# Sij2.net
KiCad netlist of a schematic drawn in EAGLE
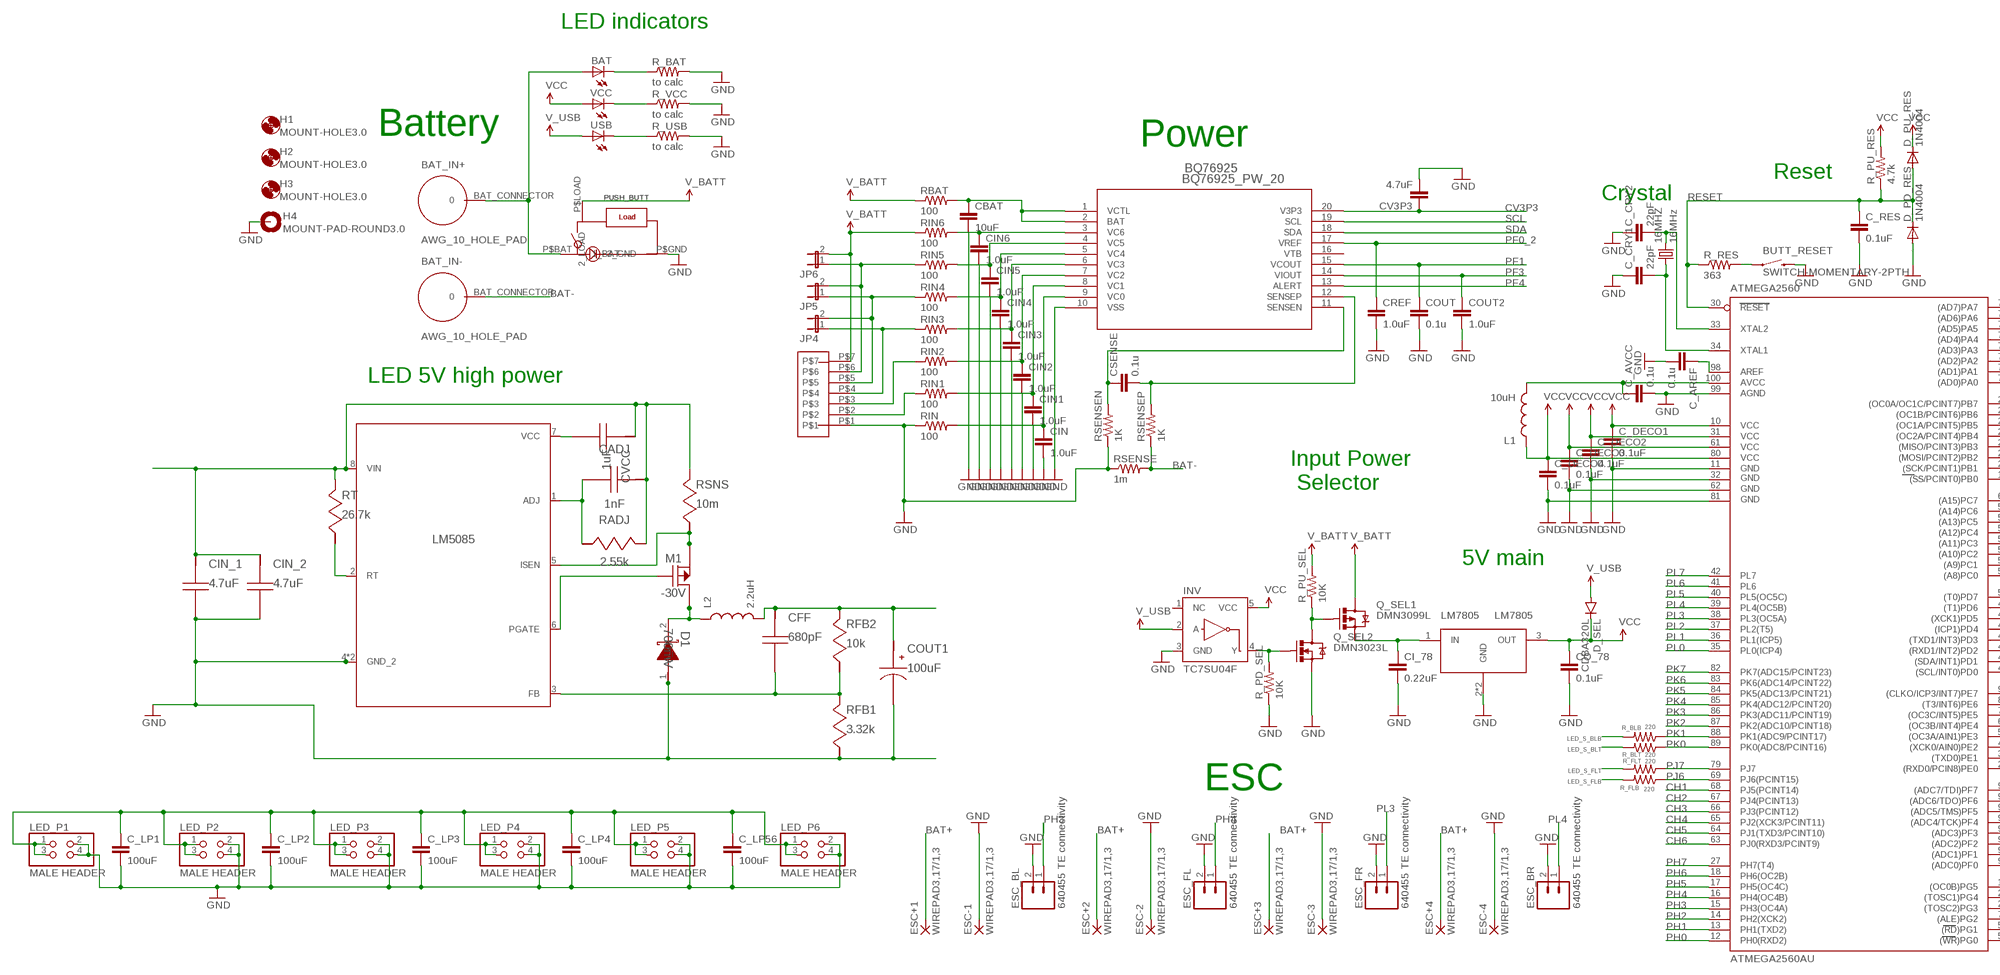
[diagram p0: schematic, sheet 1, part 1 of 2]
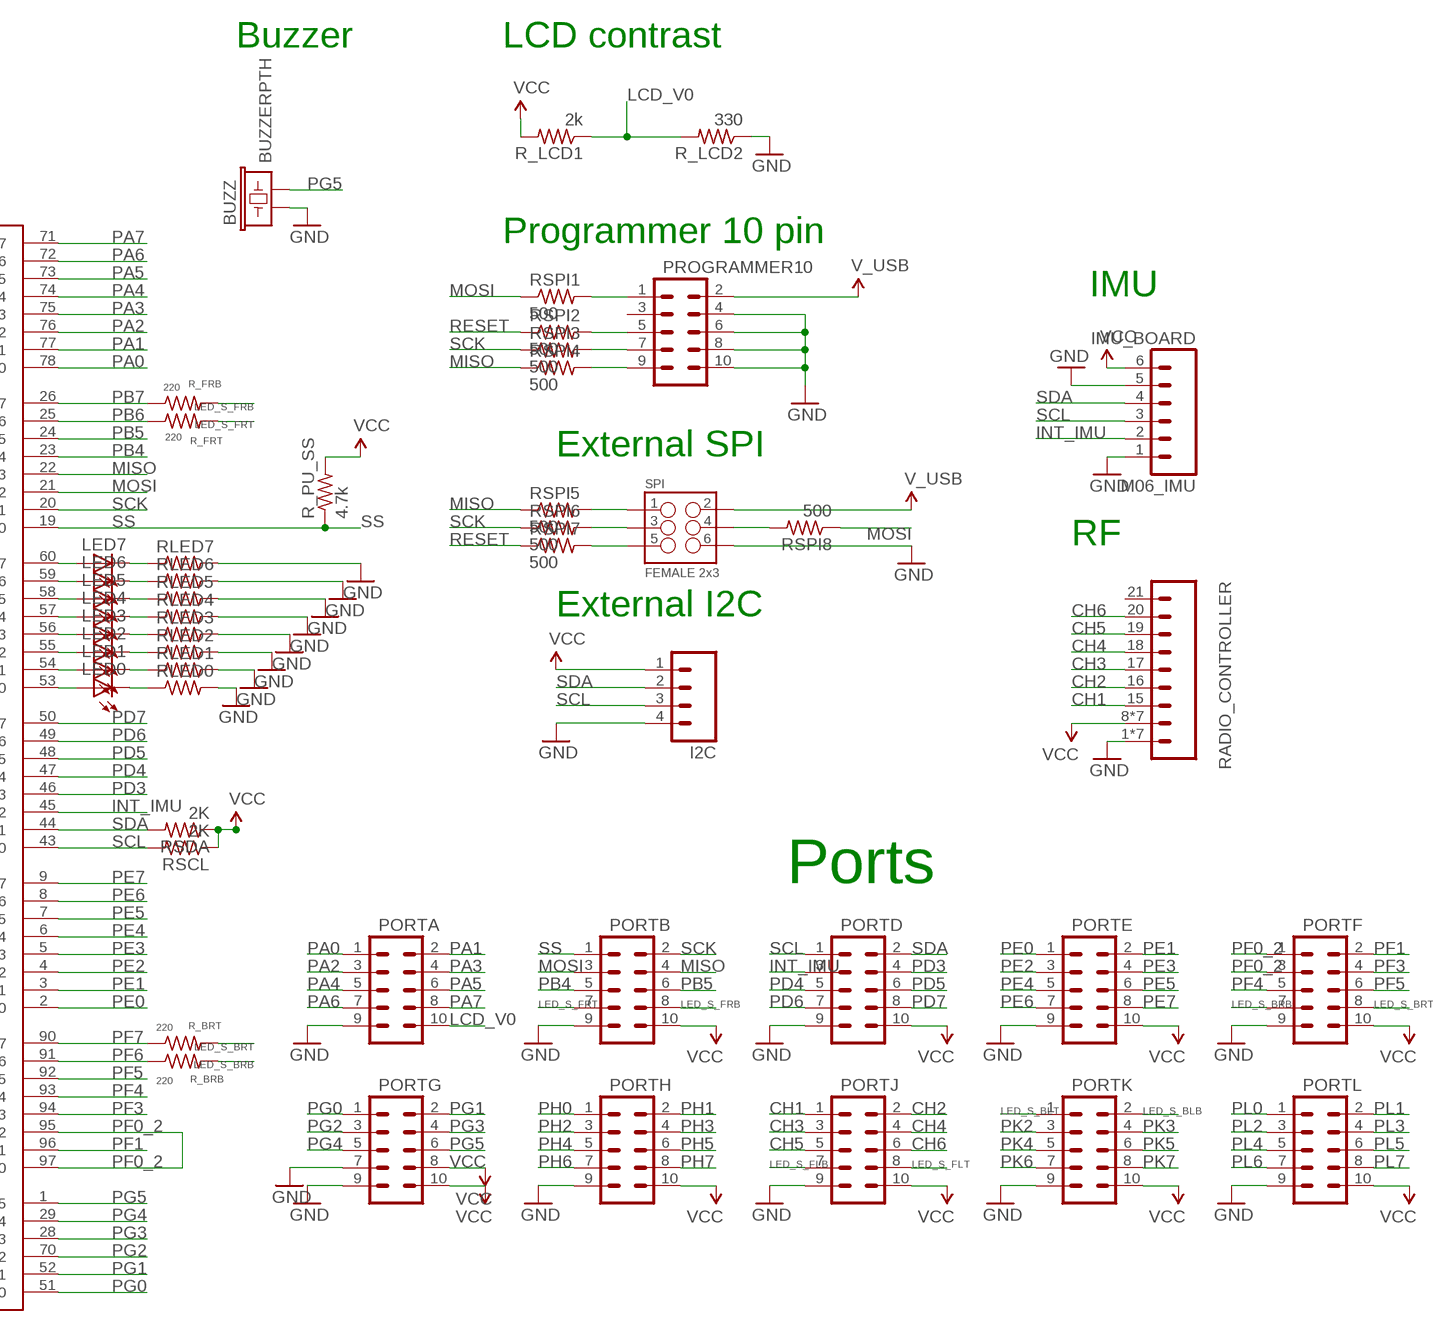
[diagram p1: schematic, sheet 1, part 2 of 2]

(export (version "E")
  (design (tool "Eeschema 10.0.6"))
  (components
    (comp (ref "16MHZ")
      (value "16MHz")
      (footprint "eagle-import:HC49US")
      (libsource (lib "eagle-import") (part "CRYSTALHC49US"))
    )
    (comp (ref "ATMEGA2560")
      (value "ATMEGA2560AU")
      (footprint "eagle-import:TQFP100")
      (libsource (lib "eagle-import") (part "ATMEGA2560AU"))
    )
    (comp (ref "BAT")
      (value "LEDCHIPLED_0805")
      (footprint "eagle-import:CHIPLED_0805")
      (libsource (lib "eagle-import") (part "LEDCHIPLED_0805"))
    )
    (comp (ref "BAT-MONIT")
      (value "7_PIN_JST-XH")
      (footprint "eagle-import:7_PIN_JST-XH")
      (libsource (lib "eagle-import") (part "7_PIN_JST-XH"))
    )
    (comp (ref "BAT_IN+")
      (value "AWG_10_HOLE_PAD")
      (footprint "eagle-import:AWG10_HOLE_PAD")
      (libsource (lib "eagle-import") (part "AWG_10_HOLE_PAD"))
    )
    (comp (ref "BAT_IN-")
      (value "AWG_10_HOLE_PAD")
      (footprint "eagle-import:AWG10_HOLE_PAD")
      (libsource (lib "eagle-import") (part "AWG_10_HOLE_PAD"))
    )
    (comp (ref "BQ76925")
      (value "BQ76925_PW_20")
      (footprint "eagle-import:PW20")
      (fields
        (field (name "GENERIC_PART_NUMBER") "BQ76925")
        (field (name "MANUFACTURER") "Texas Instruments")
        (field (name "MANUFACTURER_PART_NUMBER") "bq76925_pw_20")
      )
      (libsource (lib "eagle-import") (part "BQ76925_PW_20"))
    )
    (comp (ref "BUTT_RESET")
      (value "SWITCH-MOMENTARY-2PTH")
      (footprint "eagle-import:TACTILE-PTH")
      (libsource (lib "eagle-import") (part "SWITCH-MOMENTARY-2PTH"))
    )
    (comp (ref "BUZZ")
      (value "BUZZERPTH")
      (footprint "eagle-import:BUZZER-12MM")
      (libsource (lib "eagle-import") (part "BUZZERPTH"))
    )
    (comp (ref "CADJ")
      (value "1nF")
      (footprint "eagle-import:0201")
      (fields (field (name "MANUFACTURER_PART_NUMBER") "GRM033R71C102KA01D"))
      (libsource (lib "eagle-import") (part "GRM033R71C102KA01D"))
    )
    (comp (ref "CBAT")
      (value "10uF")
      (footprint "eagle-import:0805")
      (libsource (lib "eagle-import") (part "CAP0805"))
    )
    (comp (ref "CFF")
      (value "680pF")
      (footprint "eagle-import:0603")
      (fields (field (name "MANUFACTURER_PART_NUMBER") "GRM188R72E681KW07D"))
      (libsource (lib "eagle-import") (part "GRM188R72E681KW07D"))
    )
    (comp (ref "CIN")
      (value "1.0uF")
      (footprint "eagle-import:0603-CAP")
      (libsource (lib "eagle-import") (part "1.0UF-16V-10%(0603)"))
    )
    (comp (ref "CIN1")
      (value "1.0uF")
      (footprint "eagle-import:0603-CAP")
      (libsource (lib "eagle-import") (part "1.0UF-16V-10%(0603)"))
    )
    (comp (ref "CIN2")
      (value "1.0uF")
      (footprint "eagle-import:0603-CAP")
      (libsource (lib "eagle-import") (part "1.0UF-16V-10%(0603)"))
    )
    (comp (ref "CIN3")
      (value "1.0uF")
      (footprint "eagle-import:0603-CAP")
      (libsource (lib "eagle-import") (part "1.0UF-16V-10%(0603)"))
    )
    (comp (ref "CIN4")
      (value "1.0uF")
      (footprint "eagle-import:0603-CAP")
      (libsource (lib "eagle-import") (part "1.0UF-16V-10%(0603)"))
    )
    (comp (ref "CIN5")
      (value "1.0uF")
      (footprint "eagle-import:0603-CAP")
      (libsource (lib "eagle-import") (part "1.0UF-16V-10%(0603)"))
    )
    (comp (ref "CIN6")
      (value "1.0uF")
      (footprint "eagle-import:0603-CAP")
      (libsource (lib "eagle-import") (part "1.0UF-16V-10%(0603)"))
    )
    (comp (ref "CIN_1")
      (value "4.7uF")
      (footprint "eagle-import:0805")
      (fields (field (name "MANUFACTURER_PART_NUMBER") "GRM21BR61E475MA12L"))
      (libsource (lib "eagle-import") (part "GRM21BR61E475MA12L"))
    )
    (comp (ref "CIN_2")
      (value "4.7uF")
      (footprint "eagle-import:0805")
      (fields (field (name "MANUFACTURER_PART_NUMBER") "GRM21BR61E475MA12L"))
      (libsource (lib "eagle-import") (part "GRM21BR61E475MA12L"))
    )
    (comp (ref "CI_78")
      (value "0.22uF")
      (footprint "eagle-import:0603-CAP")
      (libsource (lib "eagle-import") (part "0.22UF-25V-10%(0603)"))
    )
    (comp (ref "COUT")
      (value "0.1u")
      (footprint "eagle-import:0603-CAP")
      (libsource (lib "eagle-import") (part "CAP0603-CAP"))
    )
    (comp (ref "COUT1")
      (value "100uF")
      (footprint "eagle-import:CAPSMT_6_A09")
      (fields (field (name "MANUFACTURER_PART_NUMBER") "6TPH100MAEA"))
      (libsource (lib "eagle-import") (part "6TPH100MAEA"))
    )
    (comp (ref "COUT2")
      (value "1.0uF")
      (footprint "eagle-import:0603-CAP")
      (libsource (lib "eagle-import") (part "1.0UF-16V-10%(0603)"))
    )
    (comp (ref "CO_78")
      (value "0.1uF")
      (footprint "eagle-import:0603-CAP")
      (libsource (lib "eagle-import") (part "0.1UF-25V-5%(0603)"))
    )
    (comp (ref "CREF")
      (value "1.0uF")
      (footprint "eagle-import:0603-CAP")
      (libsource (lib "eagle-import") (part "1.0UF-16V-10%(0603)"))
    )
    (comp (ref "CSENSE")
      (value "0.1u")
      (footprint "eagle-import:0603-CAP")
      (libsource (lib "eagle-import") (part "SparkFun-Passives_CAP0603-CAP"))
    )
    (comp (ref "CV3P3")
      (value "4.7uF")
      (footprint "eagle-import:0603-CAP")
      (libsource (lib "eagle-import") (part "4.7UF-6.3V-10%(0603)0603"))
    )
    (comp (ref "CVCC")
      (value "1uF")
      (footprint "eagle-import:0603")
      (fields (field (name "MANUFACTURER_PART_NUMBER") "GRM188R61C105KA93D"))
      (libsource (lib "eagle-import") (part "GRM188R61C105KA93D"))
    )
    (comp (ref "C_AREF")
      (value "0.1u")
      (footprint "eagle-import:0603-CAP")
      (libsource (lib "eagle-import") (part "CAP0603-CAP"))
    )
    (comp (ref "C_AVCC")
      (value "0.1u")
      (footprint "eagle-import:0603-CAP")
      (libsource (lib "eagle-import") (part "CAP0603-CAP"))
    )
    (comp (ref "C_CRY1")
      (value "22pF")
      (footprint "eagle-import:0603-CAP")
      (libsource (lib "eagle-import") (part "22PF-50V-5%(0603)"))
    )
    (comp (ref "C_CRY2")
      (value "22pF")
      (footprint "eagle-import:0603-CAP")
      (libsource (lib "eagle-import") (part "22PF-50V-5%(0603)"))
    )
    (comp (ref "C_DECO1")
      (value "0.1uF")
      (footprint "eagle-import:0603-CAP")
      (libsource (lib "eagle-import") (part "0.1UF-25V-5%(0603)"))
    )
    (comp (ref "C_DECO2")
      (value "0.1uF")
      (footprint "eagle-import:0603-CAP")
      (libsource (lib "eagle-import") (part "0.1UF-25V-5%(0603)"))
    )
    (comp (ref "C_DECO3")
      (value "0.1uF")
      (footprint "eagle-import:0603-CAP")
      (libsource (lib "eagle-import") (part "0.1UF-25V-5%(0603)"))
    )
    (comp (ref "C_DECO4")
      (value "0.1uF")
      (footprint "eagle-import:0603-CAP")
      (libsource (lib "eagle-import") (part "0.1UF-25V-5%(0603)"))
    )
    (comp (ref "C_LP1")
      (value "100uF")
      (footprint "eagle-import:1206")
      (libsource (lib "eagle-import") (part "CAP1206"))
    )
    (comp (ref "C_LP2")
      (value "100uF")
      (footprint "eagle-import:1206")
      (libsource (lib "eagle-import") (part "CAP1206"))
    )
    (comp (ref "C_LP3")
      (value "100uF")
      (footprint "eagle-import:1206")
      (libsource (lib "eagle-import") (part "CAP1206"))
    )
    (comp (ref "C_LP4")
      (value "100uF")
      (footprint "eagle-import:1206")
      (libsource (lib "eagle-import") (part "CAP1206"))
    )
    (comp (ref "C_LP56")
      (value "100uF")
      (footprint "eagle-import:1206")
      (libsource (lib "eagle-import") (part "CAP1206"))
    )
    (comp (ref "C_RES")
      (value "0.1uF")
      (footprint "eagle-import:0603-CAP")
      (libsource (lib "eagle-import") (part "0.1UF-25V-5%(0603)"))
    )
    (comp (ref "D1")
      (value "700mV")
      (footprint "eagle-import:DDPAK")
      (fields (field (name "MANUFACTURER_PART_NUMBER") "MBRB745PBF"))
      (libsource (lib "eagle-import") (part "MBRB745PBF"))
    )
    (comp (ref "D_PD_RES")
      (value "1N4004")
      (footprint "eagle-import:DO41-10")
      (libsource (lib "eagle-import") (part "1N4004"))
    )
    (comp (ref "D_PU_RES")
      (value "1N4004")
      (footprint "eagle-import:DO41-10")
      (libsource (lib "eagle-import") (part "1N4004"))
    )
    (comp (ref "D_SEL")
      (value "CDBA320L")
      (footprint "eagle-import:SMA-DIODE_ALT")
      (libsource (lib "eagle-import") (part "DIODESMA-ALT"))
    )
    (comp (ref "ESC+1")
      (value "WIREPAD3,17/1,3")
      (footprint "eagle-import:3,17_1,3")
      (libsource (lib "eagle-import") (part "WIREPAD3,17/1,3"))
    )
    (comp (ref "ESC+2")
      (value "WIREPAD3,17/1,3")
      (footprint "eagle-import:3,17_1,3")
      (libsource (lib "eagle-import") (part "WIREPAD3,17/1,3"))
    )
    (comp (ref "ESC+3")
      (value "WIREPAD3,17/1,3")
      (footprint "eagle-import:3,17_1,3")
      (libsource (lib "eagle-import") (part "WIREPAD3,17/1,3"))
    )
    (comp (ref "ESC+4")
      (value "WIREPAD3,17/1,3")
      (footprint "eagle-import:3,17_1,3")
      (libsource (lib "eagle-import") (part "WIREPAD3,17/1,3"))
    )
    (comp (ref "ESC-1")
      (value "WIREPAD3,17/1,3")
      (footprint "eagle-import:3,17_1,3")
      (libsource (lib "eagle-import") (part "WIREPAD3,17/1,3"))
    )
    (comp (ref "ESC-2")
      (value "WIREPAD3,17/1,3")
      (footprint "eagle-import:3,17_1,3")
      (libsource (lib "eagle-import") (part "WIREPAD3,17/1,3"))
    )
    (comp (ref "ESC-3")
      (value "WIREPAD3,17/1,3")
      (footprint "eagle-import:3,17_1,3")
      (libsource (lib "eagle-import") (part "WIREPAD3,17/1,3"))
    )
    (comp (ref "ESC-4")
      (value "WIREPAD3,17/1,3")
      (footprint "eagle-import:3,17_1,3")
      (libsource (lib "eagle-import") (part "WIREPAD3,17/1,3"))
    )
    (comp (ref "ESC_BL")
      (value "640455 TE connectivity")
      (footprint "eagle-import:1X02")
      (libsource (lib "eagle-import") (part "M02PTH"))
    )
    (comp (ref "ESC_BR")
      (value "640455 TE connectivity")
      (footprint "eagle-import:1X02")
      (libsource (lib "eagle-import") (part "M02PTH"))
    )
    (comp (ref "ESC_FL")
      (value "640455 TE connectivity")
      (footprint "eagle-import:1X02")
      (libsource (lib "eagle-import") (part "M02PTH"))
    )
    (comp (ref "ESC_FR")
      (value "640455 TE connectivity")
      (footprint "eagle-import:1X02")
      (libsource (lib "eagle-import") (part "M02PTH"))
    )
    (comp (ref "H1")
      (value "MOUNT-HOLE3.0")
      (footprint "eagle-import:3,0")
      (libsource (lib "eagle-import") (part "MOUNT-HOLE3.0"))
    )
    (comp (ref "H2")
      (value "MOUNT-HOLE3.0")
      (footprint "eagle-import:3,0")
      (libsource (lib "eagle-import") (part "MOUNT-HOLE3.0"))
    )
    (comp (ref "H3")
      (value "MOUNT-HOLE3.0")
      (footprint "eagle-import:3,0")
      (libsource (lib "eagle-import") (part "MOUNT-HOLE3.0"))
    )
    (comp (ref "H4")
      (value "MOUNT-PAD-ROUND3.0")
      (footprint "eagle-import:3,0-PAD")
      (libsource (lib "eagle-import") (part "MOUNT-PAD-ROUND3.0"))
    )
    (comp (ref "I2C")
      (value "M041X04_NO_SILK")
      (footprint "eagle-import:1X04_NO_SILK")
      (libsource (lib "eagle-import") (part "M041X04_NO_SILK"))
    )
    (comp (ref "IMU_BOARD")
      (value "M06_IMU")
      (footprint "eagle-import:1X06_LONGPADS")
      (libsource (lib "eagle-import") (part "M06_IMU"))
    )
    (comp (ref "INV")
      (value "TC7SU04F")
      (footprint "eagle-import:SOT23-5")
      (libsource (lib "eagle-import") (part "INVERTER_SOT23-5"))
    )
    (comp (ref "JP4")
      (value "JUMPER-2PTH")
      (footprint "eagle-import:1X02")
      (libsource (lib "eagle-import") (part "JUMPER-2PTH"))
    )
    (comp (ref "JP5")
      (value "JUMPER-2PTH")
      (footprint "eagle-import:1X02")
      (libsource (lib "eagle-import") (part "JUMPER-2PTH"))
    )
    (comp (ref "JP6")
      (value "JUMPER-2PTH")
      (footprint "eagle-import:1X02")
      (libsource (lib "eagle-import") (part "JUMPER-2PTH"))
    )
    (comp (ref "L1")
      (value "10uH")
      (footprint "eagle-import:0805")
      (libsource (lib "eagle-import") (part "INDUCTOR0805"))
    )
    (comp (ref "L2")
      (value "2.2uH")
      (footprint "eagle-import:MGV0605")
      (libsource (lib "eagle-import") (part "IND_MGV0605"))
    )
    (comp (ref "LED0")
      (value "LEDCHIPLED_0805")
      (footprint "eagle-import:CHIPLED_0805")
      (libsource (lib "eagle-import") (part "LEDCHIPLED_0805"))
    )
    (comp (ref "LED1")
      (value "LEDCHIPLED_0805")
      (footprint "eagle-import:CHIPLED_0805")
      (libsource (lib "eagle-import") (part "LEDCHIPLED_0805"))
    )
    (comp (ref "LED2")
      (value "LEDCHIPLED_0805")
      (footprint "eagle-import:CHIPLED_0805")
      (libsource (lib "eagle-import") (part "LEDCHIPLED_0805"))
    )
    (comp (ref "LED3")
      (value "LEDCHIPLED_0805")
      (footprint "eagle-import:CHIPLED_0805")
      (libsource (lib "eagle-import") (part "LEDCHIPLED_0805"))
    )
    (comp (ref "LED4")
      (value "LEDCHIPLED_0805")
      (footprint "eagle-import:CHIPLED_0805")
      (libsource (lib "eagle-import") (part "LEDCHIPLED_0805"))
    )
    (comp (ref "LED5")
      (value "LEDCHIPLED_0805")
      (footprint "eagle-import:CHIPLED_0805")
      (libsource (lib "eagle-import") (part "LEDCHIPLED_0805"))
    )
    (comp (ref "LED6")
      (value "LEDCHIPLED_0805")
      (footprint "eagle-import:CHIPLED_0805")
      (libsource (lib "eagle-import") (part "LEDCHIPLED_0805"))
    )
    (comp (ref "LED7")
      (value "LEDCHIPLED_0805")
      (footprint "eagle-import:CHIPLED_0805")
      (libsource (lib "eagle-import") (part "LEDCHIPLED_0805"))
    )
    (comp (ref "LED_P1")
      (value "MALE HEADER")
      (footprint "eagle-import:2X02")
      (libsource (lib "eagle-import") (part "PINHD-2X2"))
    )
    (comp (ref "LED_P2")
      (value "MALE HEADER")
      (footprint "eagle-import:2X02")
      (libsource (lib "eagle-import") (part "PINHD-2X2"))
    )
    (comp (ref "LED_P3")
      (value "MALE HEADER")
      (footprint "eagle-import:2X02")
      (libsource (lib "eagle-import") (part "PINHD-2X2"))
    )
    (comp (ref "LED_P4")
      (value "MALE HEADER")
      (footprint "eagle-import:2X02")
      (libsource (lib "eagle-import") (part "PINHD-2X2"))
    )
    (comp (ref "LED_P5")
      (value "MALE HEADER")
      (footprint "eagle-import:2X02")
      (libsource (lib "eagle-import") (part "PINHD-2X2"))
    )
    (comp (ref "LED_P6")
      (value "MALE HEADER")
      (footprint "eagle-import:2X02")
      (libsource (lib "eagle-import") (part "PINHD-2X2"))
    )
    (comp (ref "LM5085")
      (value "LM5085MY/NOPB")
      (footprint "eagle-import:MUY08A")
      (libsource (lib "eagle-import") (part "LM5085MY/NOPB"))
    )
    (comp (ref "LM7805")
      (value "LM7805")
      (footprint "eagle-import:KTT3")
      (libsource (lib "eagle-import") (part "LM7805"))
    )
    (comp (ref "M1")
      (value "-30V")
      (footprint "eagle-import:POWERPAK_SO-8")
      (fields (field (name "MANUFACTURER_PART_NUMBER") "Si7149DP"))
      (libsource (lib "eagle-import") (part "SI7149DP"))
    )
    (comp (ref "PORTA")
      (value "M05X2PTH")
      (footprint "eagle-import:AVR_ICSP")
      (libsource (lib "eagle-import") (part "M05X2PTH"))
    )
    (comp (ref "PORTB")
      (value "M05X2PTH")
      (footprint "eagle-import:AVR_ICSP")
      (libsource (lib "eagle-import") (part "M05X2PTH"))
    )
    (comp (ref "PORTD")
      (value "M05X2PTH")
      (footprint "eagle-import:AVR_ICSP")
      (libsource (lib "eagle-import") (part "M05X2PTH"))
    )
    (comp (ref "PORTE")
      (value "M05X2PTH")
      (footprint "eagle-import:AVR_ICSP")
      (libsource (lib "eagle-import") (part "M05X2PTH"))
    )
    (comp (ref "PORTF")
      (value "M05X2PTH")
      (footprint "eagle-import:AVR_ICSP")
      (libsource (lib "eagle-import") (part "M05X2PTH"))
    )
    (comp (ref "PORTG")
      (value "M05X2PTH")
      (footprint "eagle-import:AVR_ICSP")
      (libsource (lib "eagle-import") (part "M05X2PTH"))
    )
    (comp (ref "PORTH")
      (value "M05X2PTH")
      (footprint "eagle-import:AVR_ICSP")
      (libsource (lib "eagle-import") (part "M05X2PTH"))
    )
    (comp (ref "PORTJ")
      (value "M05X2PTH")
      (footprint "eagle-import:AVR_ICSP")
      (libsource (lib "eagle-import") (part "M05X2PTH"))
    )
    (comp (ref "PORTK")
      (value "M05X2PTH")
      (footprint "eagle-import:AVR_ICSP")
      (libsource (lib "eagle-import") (part "M05X2PTH"))
    )
    (comp (ref "PORTL")
      (value "M05X2PTH")
      (footprint "eagle-import:AVR_ICSP")
      (libsource (lib "eagle-import") (part "M05X2PTH"))
    )
    (comp (ref "PROGRAMMER10")
      (value "M05X2PTH")
      (footprint "eagle-import:AVR_ICSP")
      (libsource (lib "eagle-import") (part "M05X2PTH"))
    )
    (comp (ref "PUSH_BUTT")
      (value "PUSH_BUTTON")
      (footprint "eagle-import:PUSH_BUTTON")
      (libsource (lib "eagle-import") (part "PUSH_BUTTON"))
    )
    (comp (ref "Q_SEL1")
      (value "DMN3099L")
      (footprint "eagle-import:SOT23-3")
      (libsource (lib "eagle-import") (part "MOSFET-PCHANNEL"))
    )
    (comp (ref "Q_SEL2")
      (value "DMN3023L")
      (footprint "eagle-import:SOT23-3")
      (libsource (lib "eagle-import") (part "MOSFET-NCHANNELAO3404A"))
    )
    (comp (ref "RADIO_CONTROLLER")
      (value "RF_CONTROL_3X7_CON")
      (footprint "eagle-import:3X07")
      (libsource (lib "eagle-import") (part "RF_CONTROL_3X7_CON"))
    )
    (comp (ref "RADJ")
      (value "2.55k")
      (footprint "eagle-import:0603")
      (libsource (lib "eagle-import") (part "CRCW04022K55FKED"))
    )
    (comp (ref "RBAT")
      (value "100")
      (footprint "eagle-import:R0603")
      (libsource (lib "eagle-import") (part "R-US_R0603"))
    )
    (comp (ref "RFB1")
      (value "3.32k")
      (footprint "eagle-import:0603")
      (libsource (lib "eagle-import") (part "CRCW04023K32FKED"))
    )
    (comp (ref "RFB2")
      (value "10k")
      (footprint "eagle-import:0603")
      (libsource (lib "eagle-import") (part "CRCW040210K0FKED"))
    )
    (comp (ref "RIN")
      (value "100")
      (footprint "eagle-import:R0603")
      (libsource (lib "eagle-import") (part "R-US_R0603"))
    )
    (comp (ref "RIN1")
      (value "100")
      (footprint "eagle-import:R0603")
      (libsource (lib "eagle-import") (part "R-US_R0603"))
    )
    (comp (ref "RIN2")
      (value "100")
      (footprint "eagle-import:R0603")
      (libsource (lib "eagle-import") (part "R-US_R0603"))
    )
    (comp (ref "RIN3")
      (value "100")
      (footprint "eagle-import:R0603")
      (libsource (lib "eagle-import") (part "R-US_R0603"))
    )
    (comp (ref "RIN4")
      (value "100")
      (footprint "eagle-import:R0603")
      (libsource (lib "eagle-import") (part "R-US_R0603"))
    )
    (comp (ref "RIN5")
      (value "100")
      (footprint "eagle-import:R0603")
      (libsource (lib "eagle-import") (part "R-US_R0603"))
    )
    (comp (ref "RIN6")
      (value "100")
      (footprint "eagle-import:R0603")
      (libsource (lib "eagle-import") (part "R-US_R0603"))
    )
    (comp (ref "RLED0")
      (value "R-US_R0603")
      (footprint "eagle-import:R0603")
      (libsource (lib "eagle-import") (part "R-US_R0603"))
    )
    (comp (ref "RLED1")
      (value "R-US_R0603")
      (footprint "eagle-import:R0603")
      (libsource (lib "eagle-import") (part "R-US_R0603"))
    )
    (comp (ref "RLED2")
      (value "R-US_R0603")
      (footprint "eagle-import:R0603")
      (libsource (lib "eagle-import") (part "R-US_R0603"))
    )
    (comp (ref "RLED3")
      (value "R-US_R0603")
      (footprint "eagle-import:R0603")
      (libsource (lib "eagle-import") (part "R-US_R0603"))
    )
    (comp (ref "RLED4")
      (value "R-US_R0603")
      (footprint "eagle-import:R0603")
      (libsource (lib "eagle-import") (part "R-US_R0603"))
    )
    (comp (ref "RLED5")
      (value "R-US_R0603")
      (footprint "eagle-import:R0603")
      (libsource (lib "eagle-import") (part "R-US_R0603"))
    )
    (comp (ref "RLED6")
      (value "R-US_R0603")
      (footprint "eagle-import:R0603")
      (libsource (lib "eagle-import") (part "R-US_R0603"))
    )
    (comp (ref "RLED7")
      (value "R-US_R0603")
      (footprint "eagle-import:R0603")
      (libsource (lib "eagle-import") (part "R-US_R0603"))
    )
    (comp (ref "RSCL")
      (value "2K")
      (footprint "eagle-import:R0603")
      (libsource (lib "eagle-import") (part "R-US_R0603"))
    )
    (comp (ref "RSDA")
      (value "2K")
      (footprint "eagle-import:R0603")
      (libsource (lib "eagle-import") (part "R-US_R0603"))
    )
    (comp (ref "RSENSE")
      (value "1m")
      (footprint "eagle-import:R1206")
      (libsource (lib "eagle-import") (part "R-US_R1206"))
    )
    (comp (ref "RSENSEN")
      (value "1K")
      (footprint "eagle-import:R0603")
      (libsource (lib "eagle-import") (part "R-US_R0603"))
    )
    (comp (ref "RSENSEP")
      (value "1K")
      (footprint "eagle-import:R0603")
      (libsource (lib "eagle-import") (part "R-US_R0603"))
    )
    (comp (ref "RSNS")
      (value "10m")
      (footprint "eagle-import:1206")
      (fields
        (field (name "MANUFACTURER_PART_NUMBER") "CSR1206FK10L0")
        (field (name "POWER") "0.5")
        (field (name "TOLERANCE") "1.0")
      )
      (libsource (lib "eagle-import") (part "CSR1206FK10L0"))
    )
    (comp (ref "RSPI1")
      (value "500")
      (footprint "eagle-import:R0603")
      (libsource (lib "eagle-import") (part "R-US_R0603"))
    )
    (comp (ref "RSPI2")
      (value "500")
      (footprint "eagle-import:R0603")
      (libsource (lib "eagle-import") (part "R-US_R0603"))
    )
    (comp (ref "RSPI3")
      (value "500")
      (footprint "eagle-import:R0603")
      (libsource (lib "eagle-import") (part "R-US_R0603"))
    )
    (comp (ref "RSPI4")
      (value "500")
      (footprint "eagle-import:R0603")
      (libsource (lib "eagle-import") (part "R-US_R0603"))
    )
    (comp (ref "RSPI5")
      (value "500")
      (footprint "eagle-import:R0603")
      (libsource (lib "eagle-import") (part "R-US_R0603"))
    )
    (comp (ref "RSPI6")
      (value "500")
      (footprint "eagle-import:R0603")
      (libsource (lib "eagle-import") (part "R-US_R0603"))
    )
    (comp (ref "RSPI7")
      (value "500")
      (footprint "eagle-import:R0603")
      (libsource (lib "eagle-import") (part "R-US_R0603"))
    )
    (comp (ref "RSPI8")
      (value "500")
      (footprint "eagle-import:R0603")
      (libsource (lib "eagle-import") (part "R-US_R0603"))
    )
    (comp (ref "RT")
      (value "26.7k")
      (footprint "eagle-import:0603")
      (libsource (lib "eagle-import") (part "CRCW040226K7FKED"))
    )
    (comp (ref "R_BAT")
      (value "to calc")
      (footprint "eagle-import:R0603")
      (libsource (lib "eagle-import") (part "R-US_R0603"))
    )
    (comp (ref "R_BLB")
      (value "220")
      (footprint "eagle-import:R0603")
      (libsource (lib "eagle-import") (part "R-US_R0603"))
    )
    (comp (ref "R_BLT")
      (value "220")
      (footprint "eagle-import:R0603")
      (libsource (lib "eagle-import") (part "R-US_R0603"))
    )
    (comp (ref "R_BRB")
      (value "220")
      (footprint "eagle-import:R0603")
      (libsource (lib "eagle-import") (part "R-US_R0603"))
    )
    (comp (ref "R_BRT")
      (value "220")
      (footprint "eagle-import:R0603")
      (libsource (lib "eagle-import") (part "R-US_R0603"))
    )
    (comp (ref "R_FLB")
      (value "220")
      (footprint "eagle-import:R0603")
      (libsource (lib "eagle-import") (part "R-US_R0603"))
    )
    (comp (ref "R_FLT")
      (value "220")
      (footprint "eagle-import:R0603")
      (libsource (lib "eagle-import") (part "R-US_R0603"))
    )
    (comp (ref "R_FRB")
      (value "220")
      (footprint "eagle-import:R0603")
      (libsource (lib "eagle-import") (part "R-US_R0603"))
    )
    (comp (ref "R_FRT")
      (value "220")
      (footprint "eagle-import:R0603")
      (libsource (lib "eagle-import") (part "R-US_R0603"))
    )
    (comp (ref "R_LCD1")
      (value "2k")
      (footprint "eagle-import:R0603")
      (libsource (lib "eagle-import") (part "R-US_R0603"))
    )
    (comp (ref "R_LCD2")
      (value "330")
      (footprint "eagle-import:R0603")
      (libsource (lib "eagle-import") (part "R-US_R0603"))
    )
    (comp (ref "R_PD_SEL")
      (value "10K")
      (footprint "eagle-import:R0603")
      (libsource (lib "eagle-import") (part "R-US_R0603"))
    )
    (comp (ref "R_PU_RES")
      (value "4.7k")
      (footprint "eagle-import:R0603")
      (libsource (lib "eagle-import") (part "R-US_R0603"))
    )
    (comp (ref "R_PU_SEL")
      (value "10K")
      (footprint "eagle-import:R0603")
      (libsource (lib "eagle-import") (part "R-US_R0603"))
    )
    (comp (ref "R_PU_SS")
      (value "4.7k")
      (footprint "eagle-import:R0603")
      (libsource (lib "eagle-import") (part "R-US_R0603"))
    )
    (comp (ref "R_RES")
      (value "363")
      (footprint "eagle-import:R0603")
      (libsource (lib "eagle-import") (part "R-US_R0603"))
    )
    (comp (ref "R_USB")
      (value "to calc")
      (footprint "eagle-import:R0603")
      (libsource (lib "eagle-import") (part "R-US_R0603"))
    )
    (comp (ref "R_VCC")
      (value "to calc")
      (footprint "eagle-import:R0603")
      (libsource (lib "eagle-import") (part "R-US_R0603"))
    )
    (comp (ref "SPI")
      (value "FEMALE 2x3")
      (footprint "eagle-import:2X3")
      (libsource (lib "eagle-import") (part "M03X2FEMALE"))
    )
    (comp (ref "USB")
      (value "LEDCHIPLED_0805")
      (footprint "eagle-import:CHIPLED_0805")
      (libsource (lib "eagle-import") (part "LEDCHIPLED_0805"))
    )
    (comp (ref "VCC")
      (value "LEDCHIPLED_0805")
      (footprint "eagle-import:CHIPLED_0805")
      (libsource (lib "eagle-import") (part "LEDCHIPLED_0805"))
    )
  )
  (nets
    (net (code "1") (name "/BAT+") (class "Default")
      (node (ref "BAT") (pin "A") (pinfunction "A_A") (pintype "passive"))
      (node (ref "BAT_IN+") (pin "BAT_CONNECTOR") (pinfunction "0_BAT_CONNECTOR") (pintype "bidirectional"))
      (node (ref "ESC+1") (pin "1") (pinfunction "P_1") (pintype "passive"))
      (node (ref "ESC+2") (pin "1") (pinfunction "P_1") (pintype "passive"))
      (node (ref "ESC+3") (pin "1") (pinfunction "P_1") (pintype "passive"))
      (node (ref "ESC+4") (pin "1") (pinfunction "P_1") (pintype "passive"))
      (node (ref "PUSH_BUTT") (pin "P$BAT") (pinfunction "1_BAT_P$BAT") (pintype "bidirectional"))
    )
    (net (code "2") (name "/BAT-") (class "Default")
      (node (ref "BAT_IN-") (pin "BAT_CONNECTOR") (pinfunction "0_BAT_CONNECTOR") (pintype "bidirectional"))
      (node (ref "RSENSE") (pin "2") (pinfunction "2_2") (pintype "passive"))
      (node (ref "RSENSEP") (pin "1") (pinfunction "1_1") (pintype "passive"))
    )
    (net (code "3") (name "/CH1") (class "Default")
      (node (ref "ATMEGA2560") (pin "68") (pinfunction "PJ5(PCINT14)_68") (pintype "bidirectional"))
      (node (ref "PORTJ") (pin "1") (pinfunction "1_1") (pintype "passive"))
      (node (ref "RADIO_CONTROLLER") (pin "15") (pinfunction "1_15") (pintype "bidirectional"))
    )
    (net (code "4") (name "/CH2") (class "Default")
      (node (ref "ATMEGA2560") (pin "67") (pinfunction "PJ4(PCINT13)_67") (pintype "bidirectional"))
      (node (ref "PORTJ") (pin "2") (pinfunction "2_2") (pintype "passive"))
      (node (ref "RADIO_CONTROLLER") (pin "16") (pinfunction "2_16") (pintype "bidirectional"))
    )
    (net (code "5") (name "/CH3") (class "Default")
      (node (ref "ATMEGA2560") (pin "66") (pinfunction "PJ3(PCINT12)_66") (pintype "bidirectional"))
      (node (ref "PORTJ") (pin "3") (pinfunction "3_3") (pintype "passive"))
      (node (ref "RADIO_CONTROLLER") (pin "17") (pinfunction "3_17") (pintype "bidirectional"))
    )
    (net (code "6") (name "/CH4") (class "Default")
      (node (ref "ATMEGA2560") (pin "65") (pinfunction "PJ2(XCK3/PCINT11)_65") (pintype "bidirectional"))
      (node (ref "PORTJ") (pin "4") (pinfunction "4_4") (pintype "passive"))
      (node (ref "RADIO_CONTROLLER") (pin "18") (pinfunction "4_18") (pintype "bidirectional"))
    )
    (net (code "7") (name "/CH5") (class "Default")
      (node (ref "ATMEGA2560") (pin "64") (pinfunction "PJ1(TXD3/PCINT10)_64") (pintype "bidirectional"))
      (node (ref "PORTJ") (pin "5") (pinfunction "5_5") (pintype "passive"))
      (node (ref "RADIO_CONTROLLER") (pin "19") (pinfunction "5_19") (pintype "bidirectional"))
    )
    (net (code "8") (name "/CH6") (class "Default")
      (node (ref "ATMEGA2560") (pin "63") (pinfunction "PJ0(RXD3/PCINT9)_63") (pintype "bidirectional"))
      (node (ref "PORTJ") (pin "6") (pinfunction "6_6") (pintype "passive"))
      (node (ref "RADIO_CONTROLLER") (pin "20") (pinfunction "6_20") (pintype "bidirectional"))
    )
    (net (code "9") (name "/CV3P3") (class "Default")
      (node (ref "BQ76925") (pin "20") (pinfunction "V3P3_20") (pintype "output"))
      (node (ref "CV3P3") (pin "1") (pinfunction "1_1") (pintype "passive"))
    )
    (net (code "10") (name "/INT_IMU") (class "Default")
      (node (ref "ATMEGA2560") (pin "45") (pinfunction "(RXD1/INT2)PD2_45") (pintype "bidirectional"))
      (node (ref "IMU_BOARD") (pin "2") (pinfunction "2_2") (pintype "passive"))
      (node (ref "PORTD") (pin "3") (pinfunction "3_3") (pintype "passive"))
    )
    (net (code "11") (name "/LCD_V0") (class "Default")
      (node (ref "PORTA") (pin "10") (pinfunction "10_10") (pintype "passive"))
      (node (ref "R_LCD1") (pin "1") (pinfunction "1_1") (pintype "passive"))
      (node (ref "R_LCD2") (pin "2") (pinfunction "2_2") (pintype "passive"))
    )
    (net (code "12") (name "/LED_S_BLB") (class "Default")
      (node (ref "PORTK") (pin "2") (pinfunction "2_2") (pintype "passive"))
      (node (ref "R_BLB") (pin "2") (pinfunction "2_2") (pintype "passive"))
    )
    (net (code "13") (name "/LED_S_BLT") (class "Default")
      (node (ref "PORTK") (pin "1") (pinfunction "1_1") (pintype "passive"))
      (node (ref "R_BLT") (pin "2") (pinfunction "2_2") (pintype "passive"))
    )
    (net (code "14") (name "/LED_S_BRB") (class "Default")
      (node (ref "PORTF") (pin "7") (pinfunction "7_7") (pintype "passive"))
      (node (ref "R_BRB") (pin "2") (pinfunction "2_2") (pintype "passive"))
    )
    (net (code "15") (name "/LED_S_BRT") (class "Default")
      (node (ref "PORTF") (pin "8") (pinfunction "8_8") (pintype "passive"))
      (node (ref "R_BRT") (pin "2") (pinfunction "2_2") (pintype "passive"))
    )
    (net (code "16") (name "/LED_S_FLB") (class "Default")
      (node (ref "PORTJ") (pin "7") (pinfunction "7_7") (pintype "passive"))
      (node (ref "R_FLB") (pin "2") (pinfunction "2_2") (pintype "passive"))
    )
    (net (code "17") (name "/LED_S_FLT") (class "Default")
      (node (ref "PORTJ") (pin "8") (pinfunction "8_8") (pintype "passive"))
      (node (ref "R_FLT") (pin "2") (pinfunction "2_2") (pintype "passive"))
    )
    (net (code "18") (name "/LED_S_FRB") (class "Default")
      (node (ref "PORTB") (pin "8") (pinfunction "8_8") (pintype "passive"))
      (node (ref "R_FRB") (pin "2") (pinfunction "2_2") (pintype "passive"))
    )
    (net (code "19") (name "/LED_S_FRT") (class "Default")
      (node (ref "PORTB") (pin "7") (pinfunction "7_7") (pintype "passive"))
      (node (ref "R_FRT") (pin "2") (pinfunction "2_2") (pintype "passive"))
    )
    (net (code "20") (name "/MISO") (class "Default")
      (node (ref "ATMEGA2560") (pin "22") (pinfunction "(MISO/PCINT3)PB3_22") (pintype "bidirectional"))
      (node (ref "PORTB") (pin "4") (pinfunction "4_4") (pintype "passive"))
      (node (ref "RSPI4") (pin "1") (pinfunction "1_1") (pintype "passive"))
      (node (ref "RSPI5") (pin "1") (pinfunction "1_1") (pintype "passive"))
    )
    (net (code "21") (name "/MOSI") (class "Default")
      (node (ref "ATMEGA2560") (pin "21") (pinfunction "(MOSI/PCINT2)PB2_21") (pintype "bidirectional"))
      (node (ref "PORTB") (pin "3") (pinfunction "3_3") (pintype "passive"))
      (node (ref "RSPI1") (pin "1") (pinfunction "1_1") (pintype "passive"))
      (node (ref "RSPI8") (pin "1") (pinfunction "1_1") (pintype "passive"))
    )
    (net (code "22") (name "/PA0") (class "Default")
      (node (ref "ATMEGA2560") (pin "78") (pinfunction "(AD0)PA0_78") (pintype "bidirectional"))
      (node (ref "PORTA") (pin "1") (pinfunction "1_1") (pintype "passive"))
    )
    (net (code "23") (name "/PA1") (class "Default")
      (node (ref "ATMEGA2560") (pin "77") (pinfunction "(AD1)PA1_77") (pintype "bidirectional"))
      (node (ref "PORTA") (pin "2") (pinfunction "2_2") (pintype "passive"))
    )
    (net (code "24") (name "/PA2") (class "Default")
      (node (ref "ATMEGA2560") (pin "76") (pinfunction "(AD2)PA2_76") (pintype "bidirectional"))
      (node (ref "PORTA") (pin "3") (pinfunction "3_3") (pintype "passive"))
    )
    (net (code "25") (name "/PA3") (class "Default")
      (node (ref "ATMEGA2560") (pin "75") (pinfunction "(AD3)PA3_75") (pintype "bidirectional"))
      (node (ref "PORTA") (pin "4") (pinfunction "4_4") (pintype "passive"))
    )
    (net (code "26") (name "/PA4") (class "Default")
      (node (ref "ATMEGA2560") (pin "74") (pinfunction "(AD4)PA4_74") (pintype "bidirectional"))
      (node (ref "PORTA") (pin "5") (pinfunction "5_5") (pintype "passive"))
    )
    (net (code "27") (name "/PA5") (class "Default")
      (node (ref "ATMEGA2560") (pin "73") (pinfunction "(AD5)PA5_73") (pintype "bidirectional"))
      (node (ref "PORTA") (pin "6") (pinfunction "6_6") (pintype "passive"))
    )
    (net (code "28") (name "/PA6") (class "Default")
      (node (ref "ATMEGA2560") (pin "72") (pinfunction "(AD6)PA6_72") (pintype "bidirectional"))
      (node (ref "PORTA") (pin "7") (pinfunction "7_7") (pintype "passive"))
    )
    (net (code "29") (name "/PA7") (class "Default")
      (node (ref "ATMEGA2560") (pin "71") (pinfunction "(AD7)PA7_71") (pintype "bidirectional"))
      (node (ref "PORTA") (pin "8") (pinfunction "8_8") (pintype "passive"))
    )
    (net (code "30") (name "/PB4") (class "Default")
      (node (ref "ATMEGA2560") (pin "23") (pinfunction "(OC2A/PCINT4)PB4_23") (pintype "bidirectional"))
      (node (ref "PORTB") (pin "5") (pinfunction "5_5") (pintype "passive"))
    )
    (net (code "31") (name "/PB5") (class "Default")
      (node (ref "ATMEGA2560") (pin "24") (pinfunction "(OC1A/PCINT5)PB5_24") (pintype "bidirectional"))
      (node (ref "PORTB") (pin "6") (pinfunction "6_6") (pintype "passive"))
    )
    (net (code "32") (name "/PB6") (class "Default")
      (node (ref "ATMEGA2560") (pin "25") (pinfunction "(OC1B/PCINT6)PB6_25") (pintype "bidirectional"))
      (node (ref "R_FRT") (pin "1") (pinfunction "1_1") (pintype "passive"))
    )
    (net (code "33") (name "/PB7") (class "Default")
      (node (ref "ATMEGA2560") (pin "26") (pinfunction "(OC0A/OC1C/PCINT7)PB7_26") (pintype "bidirectional"))
      (node (ref "R_FRB") (pin "1") (pinfunction "1_1") (pintype "passive"))
    )
    (net (code "34") (name "/PD3") (class "Default")
      (node (ref "ATMEGA2560") (pin "46") (pinfunction "(TXD1/INT3)PD3_46") (pintype "bidirectional"))
      (node (ref "PORTD") (pin "4") (pinfunction "4_4") (pintype "passive"))
    )
    (net (code "35") (name "/PD4") (class "Default")
      (node (ref "ATMEGA2560") (pin "47") (pinfunction "(ICP1)PD4_47") (pintype "bidirectional"))
      (node (ref "PORTD") (pin "5") (pinfunction "5_5") (pintype "passive"))
    )
    (net (code "36") (name "/PD5") (class "Default")
      (node (ref "ATMEGA2560") (pin "48") (pinfunction "(XCK1)PD5_48") (pintype "bidirectional"))
      (node (ref "PORTD") (pin "6") (pinfunction "6_6") (pintype "passive"))
    )
    (net (code "37") (name "/PD6") (class "Default")
      (node (ref "ATMEGA2560") (pin "49") (pinfunction "(T1)PD6_49") (pintype "bidirectional"))
      (node (ref "PORTD") (pin "7") (pinfunction "7_7") (pintype "passive"))
    )
    (net (code "38") (name "/PD7") (class "Default")
      (node (ref "ATMEGA2560") (pin "50") (pinfunction "(T0)PD7_50") (pintype "bidirectional"))
      (node (ref "PORTD") (pin "8") (pinfunction "8_8") (pintype "passive"))
    )
    (net (code "39") (name "/PE0") (class "Default")
      (node (ref "ATMEGA2560") (pin "2") (pinfunction "(RXD0/PCIN8)PE0_2") (pintype "bidirectional"))
      (node (ref "PORTE") (pin "1") (pinfunction "1_1") (pintype "passive"))
    )
    (net (code "40") (name "/PE1") (class "Default")
      (node (ref "ATMEGA2560") (pin "3") (pinfunction "(TXD0)PE1_3") (pintype "bidirectional"))
      (node (ref "PORTE") (pin "2") (pinfunction "2_2") (pintype "passive"))
    )
    (net (code "41") (name "/PE2") (class "Default")
      (node (ref "ATMEGA2560") (pin "4") (pinfunction "(XCK0/AIN0)PE2_4") (pintype "bidirectional"))
      (node (ref "PORTE") (pin "3") (pinfunction "3_3") (pintype "passive"))
    )
    (net (code "42") (name "/PE3") (class "Default")
      (node (ref "ATMEGA2560") (pin "5") (pinfunction "(OC3A/AIN1)PE3_5") (pintype "bidirectional"))
      (node (ref "PORTE") (pin "4") (pinfunction "4_4") (pintype "passive"))
    )
    (net (code "43") (name "/PE4") (class "Default")
      (node (ref "ATMEGA2560") (pin "6") (pinfunction "(OC3B/INT4)PE4_6") (pintype "bidirectional"))
      (node (ref "PORTE") (pin "5") (pinfunction "5_5") (pintype "passive"))
    )
    (net (code "44") (name "/PE5") (class "Default")
      (node (ref "ATMEGA2560") (pin "7") (pinfunction "(OC3C/INT5)PE5_7") (pintype "bidirectional"))
      (node (ref "PORTE") (pin "6") (pinfunction "6_6") (pintype "passive"))
    )
    (net (code "45") (name "/PE6") (class "Default")
      (node (ref "ATMEGA2560") (pin "8") (pinfunction "(T3/INT6)PE6_8") (pintype "bidirectional"))
      (node (ref "PORTE") (pin "7") (pinfunction "7_7") (pintype "passive"))
    )
    (net (code "46") (name "/PE7") (class "Default")
      (node (ref "ATMEGA2560") (pin "9") (pinfunction "(CLKO/ICP3/INT7)PE7_9") (pintype "bidirectional"))
      (node (ref "PORTE") (pin "8") (pinfunction "8_8") (pintype "passive"))
    )
    (net (code "47") (name "/PF0_2") (class "Default")
      (node (ref "ATMEGA2560") (pin "95") (pinfunction "(ADC2)PF2_95") (pintype "bidirectional"))
      (node (ref "ATMEGA2560") (pin "97") (pinfunction "(ADC0)PF0_97") (pintype "bidirectional"))
      (node (ref "BQ76925") (pin "17") (pinfunction "VREF_17") (pintype "output"))
      (node (ref "CREF") (pin "1") (pinfunction "1_1") (pintype "passive"))
      (node (ref "PORTF") (pin "1") (pinfunction "1_1") (pintype "passive"))
      (node (ref "PORTF") (pin "3") (pinfunction "3_3") (pintype "passive"))
    )
    (net (code "48") (name "/PF1") (class "Default")
      (node (ref "ATMEGA2560") (pin "96") (pinfunction "(ADC1)PF1_96") (pintype "bidirectional"))
      (node (ref "BQ76925") (pin "15") (pinfunction "VCOUT_15") (pintype "output"))
      (node (ref "COUT") (pin "1") (pinfunction "1_1") (pintype "passive"))
      (node (ref "PORTF") (pin "2") (pinfunction "2_2") (pintype "passive"))
    )
    (net (code "49") (name "/PF3") (class "Default")
      (node (ref "ATMEGA2560") (pin "94") (pinfunction "(ADC3)PF3_94") (pintype "bidirectional"))
      (node (ref "BQ76925") (pin "14") (pinfunction "VIOUT_14") (pintype "output"))
      (node (ref "COUT2") (pin "1") (pinfunction "1_1") (pintype "passive"))
      (node (ref "PORTF") (pin "4") (pinfunction "4_4") (pintype "passive"))
    )
    (net (code "50") (name "/PF4") (class "Default")
      (node (ref "ATMEGA2560") (pin "93") (pinfunction "(ADC4/TCK)PF4_93") (pintype "bidirectional"))
      (node (ref "BQ76925") (pin "13") (pinfunction "ALERT_13") (pintype "output"))
      (node (ref "PORTF") (pin "5") (pinfunction "5_5") (pintype "passive"))
    )
    (net (code "51") (name "/PF5") (class "Default")
      (node (ref "ATMEGA2560") (pin "92") (pinfunction "(ADC5/TMS)PF5_92") (pintype "bidirectional"))
      (node (ref "PORTF") (pin "6") (pinfunction "6_6") (pintype "passive"))
    )
    (net (code "52") (name "/PF6") (class "Default")
      (node (ref "ATMEGA2560") (pin "91") (pinfunction "(ADC6/TDO)PF6_91") (pintype "bidirectional"))
      (node (ref "R_BRB") (pin "1") (pinfunction "1_1") (pintype "passive"))
    )
    (net (code "53") (name "/PF7") (class "Default")
      (node (ref "ATMEGA2560") (pin "90") (pinfunction "(ADC7/TDI)PF7_90") (pintype "bidirectional"))
      (node (ref "R_BRT") (pin "1") (pinfunction "1_1") (pintype "passive"))
    )
    (net (code "54") (name "/PG0") (class "Default")
      (node (ref "ATMEGA2560") (pin "51") (pinfunction "(WR)PG0_51") (pintype "bidirectional"))
      (node (ref "PORTG") (pin "1") (pinfunction "1_1") (pintype "passive"))
    )
    (net (code "55") (name "/PG1") (class "Default")
      (node (ref "ATMEGA2560") (pin "52") (pinfunction "(RD)PG1_52") (pintype "bidirectional"))
      (node (ref "PORTG") (pin "2") (pinfunction "2_2") (pintype "passive"))
    )
    (net (code "56") (name "/PG2") (class "Default")
      (node (ref "ATMEGA2560") (pin "70") (pinfunction "(ALE)PG2_70") (pintype "bidirectional"))
      (node (ref "PORTG") (pin "3") (pinfunction "3_3") (pintype "passive"))
    )
    (net (code "57") (name "/PG3") (class "Default")
      (node (ref "ATMEGA2560") (pin "28") (pinfunction "(TOSC2)PG3_28") (pintype "bidirectional"))
      (node (ref "PORTG") (pin "4") (pinfunction "4_4") (pintype "passive"))
    )
    (net (code "58") (name "/PG4") (class "Default")
      (node (ref "ATMEGA2560") (pin "29") (pinfunction "(TOSC1)PG4_29") (pintype "bidirectional"))
      (node (ref "PORTG") (pin "5") (pinfunction "5_5") (pintype "passive"))
    )
    (net (code "59") (name "/PG5") (class "Default")
      (node (ref "ATMEGA2560") (pin "1") (pinfunction "(OC0B)PG5_1") (pintype "bidirectional"))
      (node (ref "BUZZ") (pin "-") (pinfunction "2_-") (pintype "passive"))
      (node (ref "PORTG") (pin "6") (pinfunction "6_6") (pintype "passive"))
    )
    (net (code "60") (name "/PH0") (class "Default")
      (node (ref "ATMEGA2560") (pin "12") (pinfunction "PH0(RXD2)_12") (pintype "bidirectional"))
      (node (ref "PORTH") (pin "1") (pinfunction "1_1") (pintype "passive"))
    )
    (net (code "61") (name "/PH1") (class "Default")
      (node (ref "ATMEGA2560") (pin "13") (pinfunction "PH1(TXD2)_13") (pintype "bidirectional"))
      (node (ref "PORTH") (pin "2") (pinfunction "2_2") (pintype "passive"))
    )
    (net (code "62") (name "/PH2") (class "Default")
      (node (ref "ATMEGA2560") (pin "14") (pinfunction "PH2(XCK2)_14") (pintype "bidirectional"))
      (node (ref "PORTH") (pin "3") (pinfunction "3_3") (pintype "passive"))
    )
    (net (code "63") (name "/PH3") (class "Default")
      (node (ref "ATMEGA2560") (pin "15") (pinfunction "PH3(OC4A)_15") (pintype "bidirectional"))
      (node (ref "ESC_BL") (pin "1") (pinfunction "1_1") (pintype "passive"))
      (node (ref "PORTH") (pin "4") (pinfunction "4_4") (pintype "passive"))
    )
    (net (code "64") (name "/PH4") (class "Default")
      (node (ref "ATMEGA2560") (pin "16") (pinfunction "PH4(OC4B)_16") (pintype "bidirectional"))
      (node (ref "ESC_FL") (pin "1") (pinfunction "1_1") (pintype "passive"))
      (node (ref "PORTH") (pin "5") (pinfunction "5_5") (pintype "passive"))
    )
    (net (code "65") (name "/PH5") (class "Default")
      (node (ref "ATMEGA2560") (pin "17") (pinfunction "PH5(OC4C)_17") (pintype "bidirectional"))
      (node (ref "PORTH") (pin "6") (pinfunction "6_6") (pintype "passive"))
    )
    (net (code "66") (name "/PH6") (class "Default")
      (node (ref "ATMEGA2560") (pin "18") (pinfunction "PH6(OC2B)_18") (pintype "bidirectional"))
      (node (ref "PORTH") (pin "7") (pinfunction "7_7") (pintype "passive"))
    )
    (net (code "67") (name "/PH7") (class "Default")
      (node (ref "ATMEGA2560") (pin "27") (pinfunction "PH7(T4)_27") (pintype "bidirectional"))
      (node (ref "PORTH") (pin "8") (pinfunction "8_8") (pintype "passive"))
    )
    (net (code "68") (name "/PJ6") (class "Default")
      (node (ref "ATMEGA2560") (pin "69") (pinfunction "PJ6(PCINT15)_69") (pintype "bidirectional"))
      (node (ref "R_FLB") (pin "1") (pinfunction "1_1") (pintype "passive"))
    )
    (net (code "69") (name "/PJ7") (class "Default")
      (node (ref "ATMEGA2560") (pin "79") (pinfunction "PJ7_79") (pintype "bidirectional"))
      (node (ref "R_FLT") (pin "1") (pinfunction "1_1") (pintype "passive"))
    )
    (net (code "70") (name "/PK0") (class "Default")
      (node (ref "ATMEGA2560") (pin "89") (pinfunction "PK0(ADC8/PCINT16)_89") (pintype "bidirectional"))
      (node (ref "R_BLT") (pin "1") (pinfunction "1_1") (pintype "passive"))
    )
    (net (code "71") (name "/PK1") (class "Default")
      (node (ref "ATMEGA2560") (pin "88") (pinfunction "PK1(ADC9/PCINT17)_88") (pintype "bidirectional"))
      (node (ref "R_BLB") (pin "1") (pinfunction "1_1") (pintype "passive"))
    )
    (net (code "72") (name "/PK2") (class "Default")
      (node (ref "ATMEGA2560") (pin "87") (pinfunction "PK2(ADC10/PCINT18)_87") (pintype "bidirectional"))
      (node (ref "PORTK") (pin "3") (pinfunction "3_3") (pintype "passive"))
    )
    (net (code "73") (name "/PK3") (class "Default")
      (node (ref "ATMEGA2560") (pin "86") (pinfunction "PK3(ADC11/PCINT19)_86") (pintype "bidirectional"))
      (node (ref "PORTK") (pin "4") (pinfunction "4_4") (pintype "passive"))
    )
    (net (code "74") (name "/PK4") (class "Default")
      (node (ref "ATMEGA2560") (pin "85") (pinfunction "PK4(ADC12/PCINT20)_85") (pintype "bidirectional"))
      (node (ref "PORTK") (pin "5") (pinfunction "5_5") (pintype "passive"))
    )
    (net (code "75") (name "/PK5") (class "Default")
      (node (ref "ATMEGA2560") (pin "84") (pinfunction "PK5(ADC13/PCINT21)_84") (pintype "bidirectional"))
      (node (ref "PORTK") (pin "6") (pinfunction "6_6") (pintype "passive"))
    )
    (net (code "76") (name "/PK6") (class "Default")
      (node (ref "ATMEGA2560") (pin "83") (pinfunction "PK6(ADC14/PCINT22)_83") (pintype "bidirectional"))
      (node (ref "PORTK") (pin "7") (pinfunction "7_7") (pintype "passive"))
    )
    (net (code "77") (name "/PK7") (class "Default")
      (node (ref "ATMEGA2560") (pin "82") (pinfunction "PK7(ADC15/PCINT23)_82") (pintype "bidirectional"))
      (node (ref "PORTK") (pin "8") (pinfunction "8_8") (pintype "passive"))
    )
    (net (code "78") (name "/PL0") (class "Default")
      (node (ref "ATMEGA2560") (pin "35") (pinfunction "PL0(ICP4)_35") (pintype "bidirectional"))
      (node (ref "PORTL") (pin "1") (pinfunction "1_1") (pintype "passive"))
    )
    (net (code "79") (name "/PL1") (class "Default")
      (node (ref "ATMEGA2560") (pin "36") (pinfunction "PL1(ICP5)_36") (pintype "bidirectional"))
      (node (ref "PORTL") (pin "2") (pinfunction "2_2") (pintype "passive"))
    )
    (net (code "80") (name "/PL2") (class "Default")
      (node (ref "ATMEGA2560") (pin "37") (pinfunction "PL2(T5)_37") (pintype "bidirectional"))
      (node (ref "PORTL") (pin "3") (pinfunction "3_3") (pintype "passive"))
    )
    (net (code "81") (name "/PL3") (class "Default")
      (node (ref "ATMEGA2560") (pin "38") (pinfunction "PL3(OC5A)_38") (pintype "bidirectional"))
      (node (ref "ESC_FR") (pin "1") (pinfunction "1_1") (pintype "passive"))
      (node (ref "PORTL") (pin "4") (pinfunction "4_4") (pintype "passive"))
    )
    (net (code "82") (name "/PL4") (class "Default")
      (node (ref "ATMEGA2560") (pin "39") (pinfunction "PL4(OC5B)_39") (pintype "bidirectional"))
      (node (ref "ESC_BR") (pin "1") (pinfunction "1_1") (pintype "passive"))
      (node (ref "PORTL") (pin "5") (pinfunction "5_5") (pintype "passive"))
    )
    (net (code "83") (name "/PL5") (class "Default")
      (node (ref "ATMEGA2560") (pin "40") (pinfunction "PL5(OC5C)_40") (pintype "bidirectional"))
      (node (ref "PORTL") (pin "6") (pinfunction "6_6") (pintype "passive"))
    )
    (net (code "84") (name "/PL6") (class "Default")
      (node (ref "ATMEGA2560") (pin "41") (pinfunction "PL6_41") (pintype "bidirectional"))
      (node (ref "PORTL") (pin "7") (pinfunction "7_7") (pintype "passive"))
    )
    (net (code "85") (name "/PL7") (class "Default")
      (node (ref "ATMEGA2560") (pin "42") (pinfunction "PL7_42") (pintype "bidirectional"))
      (node (ref "PORTL") (pin "8") (pinfunction "8_8") (pintype "passive"))
    )
    (net (code "86") (name "/RESET") (class "Default")
      (node (ref "ATMEGA2560") (pin "30") (pinfunction "RESET_30") (pintype "input"))
      (node (ref "C_RES") (pin "1") (pinfunction "1_1") (pintype "passive"))
      (node (ref "D_PD_RES") (pin "C") (pinfunction "C_C") (pintype "passive"))
      (node (ref "D_PU_RES") (pin "A") (pinfunction "A_A") (pintype "passive"))
      (node (ref "RSPI2") (pin "1") (pinfunction "1_1") (pintype "passive"))
      (node (ref "RSPI7") (pin "1") (pinfunction "1_1") (pintype "passive"))
      (node (ref "R_PU_RES") (pin "1") (pinfunction "1_1") (pintype "passive"))
      (node (ref "R_RES") (pin "1") (pinfunction "1_1") (pintype "passive"))
    )
    (net (code "87") (name "/SCK") (class "Default")
      (node (ref "ATMEGA2560") (pin "20") (pinfunction "(SCK/PCINT1)PB1_20") (pintype "bidirectional"))
      (node (ref "PORTB") (pin "2") (pinfunction "2_2") (pintype "passive"))
      (node (ref "RSPI3") (pin "1") (pinfunction "1_1") (pintype "passive"))
      (node (ref "RSPI6") (pin "1") (pinfunction "1_1") (pintype "passive"))
    )
    (net (code "88") (name "/SCL") (class "Default")
      (node (ref "ATMEGA2560") (pin "43") (pinfunction "(SCL/INT0)PD0_43") (pintype "bidirectional"))
      (node (ref "BQ76925") (pin "19") (pinfunction "SCL_19") (pintype "input"))
      (node (ref "I2C") (pin "3") (pinfunction "3_3") (pintype "passive"))
      (node (ref "IMU_BOARD") (pin "3") (pinfunction "3_3") (pintype "passive"))
      (node (ref "PORTD") (pin "1") (pinfunction "1_1") (pintype "passive"))
      (node (ref "RSCL") (pin "2") (pinfunction "2_2") (pintype "passive"))
    )
    (net (code "89") (name "/SDA") (class "Default")
      (node (ref "ATMEGA2560") (pin "44") (pinfunction "(SDA/INT1)PD1_44") (pintype "bidirectional"))
      (node (ref "BQ76925") (pin "18") (pinfunction "SDA_18") (pintype "bidirectional"))
      (node (ref "I2C") (pin "2") (pinfunction "2_2") (pintype "passive"))
      (node (ref "IMU_BOARD") (pin "4") (pinfunction "4_4") (pintype "passive"))
      (node (ref "PORTD") (pin "2") (pinfunction "2_2") (pintype "passive"))
      (node (ref "RSDA") (pin "2") (pinfunction "2_2") (pintype "passive"))
    )
    (net (code "90") (name "/SS") (class "Default")
      (node (ref "ATMEGA2560") (pin "19") (pinfunction "(SS/PCINT0)PB0_19") (pintype "bidirectional"))
      (node (ref "PORTB") (pin "1") (pinfunction "1_1") (pintype "passive"))
      (node (ref "R_PU_SS") (pin "1") (pinfunction "1_1") (pintype "passive"))
    )
    (net (code "91") (name "/VOUT_5085") (class "Default")
      (node (ref "CFF") (pin "1") (pinfunction "1_1") (pintype "passive"))
      (node (ref "COUT1") (pin "1") (pinfunction "+_1") (pintype "passive"))
      (node (ref "C_LP1") (pin "1") (pinfunction "1_1") (pintype "passive"))
      (node (ref "C_LP2") (pin "1") (pinfunction "1_1") (pintype "passive"))
      (node (ref "C_LP3") (pin "1") (pinfunction "1_1") (pintype "passive"))
      (node (ref "C_LP4") (pin "1") (pinfunction "1_1") (pintype "passive"))
      (node (ref "C_LP56") (pin "1") (pinfunction "1_1") (pintype "passive"))
      (node (ref "L2") (pin "P$2") (pinfunction "2_P$2") (pintype "passive"))
      (node (ref "LED_P1") (pin "1") (pinfunction "1_1") (pintype "passive"))
      (node (ref "LED_P1") (pin "3") (pinfunction "3_3") (pintype "passive"))
      (node (ref "LED_P2") (pin "1") (pinfunction "1_1") (pintype "passive"))
      (node (ref "LED_P2") (pin "3") (pinfunction "3_3") (pintype "passive"))
      (node (ref "LED_P3") (pin "1") (pinfunction "1_1") (pintype "passive"))
      (node (ref "LED_P3") (pin "3") (pinfunction "3_3") (pintype "passive"))
      (node (ref "LED_P4") (pin "1") (pinfunction "1_1") (pintype "passive"))
      (node (ref "LED_P4") (pin "3") (pinfunction "3_3") (pintype "passive"))
      (node (ref "LED_P5") (pin "1") (pinfunction "1_1") (pintype "passive"))
      (node (ref "LED_P5") (pin "3") (pinfunction "3_3") (pintype "passive"))
      (node (ref "LED_P6") (pin "1") (pinfunction "1_1") (pintype "passive"))
      (node (ref "LED_P6") (pin "3") (pinfunction "3_3") (pintype "passive"))
      (node (ref "RFB2") (pin "1") (pinfunction "1_1") (pintype "passive"))
    )
    (net (code "92") (name "GND") (class "Default")
      (node (ref "ATMEGA2560") (pin "11") (pinfunction "GND_11") (pintype "power_in"))
      (node (ref "ATMEGA2560") (pin "32") (pinfunction "GND1_32") (pintype "power_in"))
      (node (ref "ATMEGA2560") (pin "62") (pinfunction "GND2_62") (pintype "power_in"))
      (node (ref "ATMEGA2560") (pin "81") (pinfunction "GND3_81") (pintype "power_in"))
      (node (ref "ATMEGA2560") (pin "99") (pinfunction "AGND_99") (pintype "power_in"))
      (node (ref "BAT-MONIT") (pin "P$1") (pinfunction "P$1_P$1") (pintype "bidirectional"))
      (node (ref "BQ76925") (pin "10") (pinfunction "VSS_10") (pintype "power_in"))
      (node (ref "BUTT_RESET") (pin "3") (pinfunction "2_3") (pintype "passive"))
      (node (ref "BUTT_RESET") (pin "4") (pinfunction "2_4") (pintype "passive"))
      (node (ref "BUZZ") (pin "+") (pinfunction "1_+") (pintype "passive"))
      (node (ref "CBAT") (pin "2") (pinfunction "2_2") (pintype "passive"))
      (node (ref "CIN") (pin "2") (pinfunction "2_2") (pintype "passive"))
      (node (ref "CIN1") (pin "2") (pinfunction "2_2") (pintype "passive"))
      (node (ref "CIN2") (pin "2") (pinfunction "2_2") (pintype "passive"))
      (node (ref "CIN3") (pin "2") (pinfunction "2_2") (pintype "passive"))
      (node (ref "CIN4") (pin "2") (pinfunction "2_2") (pintype "passive"))
      (node (ref "CIN5") (pin "2") (pinfunction "2_2") (pintype "passive"))
      (node (ref "CIN6") (pin "2") (pinfunction "2_2") (pintype "passive"))
      (node (ref "CIN_1") (pin "2") (pinfunction "2_2") (pintype "passive"))
      (node (ref "CIN_2") (pin "2") (pinfunction "2_2") (pintype "passive"))
      (node (ref "CI_78") (pin "2") (pinfunction "2_2") (pintype "passive"))
      (node (ref "COUT") (pin "2") (pinfunction "2_2") (pintype "passive"))
      (node (ref "COUT1") (pin "2") (pinfunction "-_2") (pintype "passive"))
      (node (ref "COUT2") (pin "2") (pinfunction "2_2") (pintype "passive"))
      (node (ref "CO_78") (pin "2") (pinfunction "2_2") (pintype "passive"))
      (node (ref "CREF") (pin "2") (pinfunction "2_2") (pintype "passive"))
      (node (ref "CV3P3") (pin "2") (pinfunction "2_2") (pintype "passive"))
      (node (ref "C_AREF") (pin "2") (pinfunction "2_2") (pintype "passive"))
      (node (ref "C_AVCC") (pin "2") (pinfunction "2_2") (pintype "passive"))
      (node (ref "C_CRY1") (pin "1") (pinfunction "1_1") (pintype "passive"))
      (node (ref "C_CRY2") (pin "1") (pinfunction "1_1") (pintype "passive"))
      (node (ref "C_DECO1") (pin "2") (pinfunction "2_2") (pintype "passive"))
      (node (ref "C_DECO2") (pin "2") (pinfunction "2_2") (pintype "passive"))
      (node (ref "C_DECO3") (pin "2") (pinfunction "2_2") (pintype "passive"))
      (node (ref "C_DECO4") (pin "2") (pinfunction "2_2") (pintype "passive"))
      (node (ref "C_LP1") (pin "2") (pinfunction "2_2") (pintype "passive"))
      (node (ref "C_LP2") (pin "2") (pinfunction "2_2") (pintype "passive"))
      (node (ref "C_LP3") (pin "2") (pinfunction "2_2") (pintype "passive"))
      (node (ref "C_LP4") (pin "2") (pinfunction "2_2") (pintype "passive"))
      (node (ref "C_LP56") (pin "2") (pinfunction "2_2") (pintype "passive"))
      (node (ref "C_RES") (pin "2") (pinfunction "2_2") (pintype "passive"))
      (node (ref "D1") (pin "1") (pinfunction "A_2_1") (pintype "passive"))
      (node (ref "D_PD_RES") (pin "A") (pinfunction "A_A") (pintype "passive"))
      (node (ref "ESC-1") (pin "1") (pinfunction "P_1") (pintype "passive"))
      (node (ref "ESC-2") (pin "1") (pinfunction "P_1") (pintype "passive"))
      (node (ref "ESC-3") (pin "1") (pinfunction "P_1") (pintype "passive"))
      (node (ref "ESC-4") (pin "1") (pinfunction "P_1") (pintype "passive"))
      (node (ref "ESC_BL") (pin "2") (pinfunction "2_2") (pintype "passive"))
      (node (ref "ESC_BR") (pin "2") (pinfunction "2_2") (pintype "passive"))
      (node (ref "ESC_FL") (pin "2") (pinfunction "2_2") (pintype "passive"))
      (node (ref "ESC_FR") (pin "2") (pinfunction "2_2") (pintype "passive"))
      (node (ref "H4") (pin "B3,0") (pinfunction "MOUNT_B3,0") (pintype "passive"))
      (node (ref "I2C") (pin "4") (pinfunction "4_4") (pintype "passive"))
      (node (ref "IMU_BOARD") (pin "1") (pinfunction "1_1") (pintype "passive"))
      (node (ref "IMU_BOARD") (pin "5") (pinfunction "5_5") (pintype "passive"))
      (node (ref "INV") (pin "3") (pinfunction "GND_3") (pintype "bidirectional"))
      (node (ref "LED_P1") (pin "2") (pinfunction "2_2") (pintype "passive"))
      (node (ref "LED_P1") (pin "4") (pinfunction "4_4") (pintype "passive"))
      (node (ref "LED_P2") (pin "2") (pinfunction "2_2") (pintype "passive"))
      (node (ref "LED_P2") (pin "4") (pinfunction "4_4") (pintype "passive"))
      (node (ref "LED_P3") (pin "2") (pinfunction "2_2") (pintype "passive"))
      (node (ref "LED_P3") (pin "4") (pinfunction "4_4") (pintype "passive"))
      (node (ref "LED_P4") (pin "2") (pinfunction "2_2") (pintype "passive"))
      (node (ref "LED_P4") (pin "4") (pinfunction "4_4") (pintype "passive"))
      (node (ref "LED_P5") (pin "2") (pinfunction "2_2") (pintype "passive"))
      (node (ref "LED_P5") (pin "4") (pinfunction "4_4") (pintype "passive"))
      (node (ref "LED_P6") (pin "2") (pinfunction "2_2") (pintype "passive"))
      (node (ref "LED_P6") (pin "4") (pinfunction "4_4") (pintype "passive"))
      (node (ref "LM5085") (pin "4") (pinfunction "GND_2_4") (pintype "passive"))
      (node (ref "LM5085") (pin "9") (pinfunction "GND_2_9") (pintype "passive"))
      (node (ref "LM7805") (pin "2") (pinfunction "GND_2") (pintype "bidirectional"))
      (node (ref "LM7805") (pin "4") (pinfunction "GND_4") (pintype "bidirectional"))
      (node (ref "PORTA") (pin "9") (pinfunction "9_9") (pintype "passive"))
      (node (ref "PORTB") (pin "9") (pinfunction "9_9") (pintype "passive"))
      (node (ref "PORTD") (pin "9") (pinfunction "9_9") (pintype "passive"))
      (node (ref "PORTE") (pin "9") (pinfunction "9_9") (pintype "passive"))
      (node (ref "PORTF") (pin "9") (pinfunction "9_9") (pintype "passive"))
      (node (ref "PORTG") (pin "7") (pinfunction "7_7") (pintype "passive"))
      (node (ref "PORTG") (pin "9") (pinfunction "9_9") (pintype "passive"))
      (node (ref "PORTH") (pin "9") (pinfunction "9_9") (pintype "passive"))
      (node (ref "PORTJ") (pin "9") (pinfunction "9_9") (pintype "passive"))
      (node (ref "PORTK") (pin "9") (pinfunction "9_9") (pintype "passive"))
      (node (ref "PORTL") (pin "9") (pinfunction "9_9") (pintype "passive"))
      (node (ref "PROGRAMMER10") (pin "10") (pinfunction "10_10") (pintype "passive"))
      (node (ref "PROGRAMMER10") (pin "4") (pinfunction "4_4") (pintype "passive"))
      (node (ref "PROGRAMMER10") (pin "6") (pinfunction "6_6") (pintype "passive"))
      (node (ref "PROGRAMMER10") (pin "8") (pinfunction "8_8") (pintype "passive"))
      (node (ref "PUSH_BUTT") (pin "P$GND") (pinfunction "3_GND_P$GND") (pintype "bidirectional"))
      (node (ref "Q_SEL2") (pin "2") (pinfunction "S_2") (pintype "passive"))
      (node (ref "RADIO_CONTROLLER") (pin "1") (pinfunction "GND_1") (pintype "power_in"))
      (node (ref "RADIO_CONTROLLER") (pin "2") (pinfunction "GND_2") (pintype "power_in"))
      (node (ref "RADIO_CONTROLLER") (pin "3") (pinfunction "GND_3") (pintype "power_in"))
      (node (ref "RADIO_CONTROLLER") (pin "4") (pinfunction "GND_4") (pintype "power_in"))
      (node (ref "RADIO_CONTROLLER") (pin "5") (pinfunction "GND_5") (pintype "power_in"))
      (node (ref "RADIO_CONTROLLER") (pin "6") (pinfunction "GND_6") (pintype "power_in"))
      (node (ref "RADIO_CONTROLLER") (pin "7") (pinfunction "GND_7") (pintype "power_in"))
      (node (ref "RFB1") (pin "2") (pinfunction "2_2") (pintype "passive"))
      (node (ref "RIN") (pin "1") (pinfunction "1_1") (pintype "passive"))
      (node (ref "RLED0") (pin "2") (pinfunction "2_2") (pintype "passive"))
      (node (ref "RLED1") (pin "2") (pinfunction "2_2") (pintype "passive"))
      (node (ref "RLED2") (pin "2") (pinfunction "2_2") (pintype "passive"))
      (node (ref "RLED3") (pin "2") (pinfunction "2_2") (pintype "passive"))
      (node (ref "RLED4") (pin "2") (pinfunction "2_2") (pintype "passive"))
      (node (ref "RLED5") (pin "2") (pinfunction "2_2") (pintype "passive"))
      (node (ref "RLED6") (pin "2") (pinfunction "2_2") (pintype "passive"))
      (node (ref "RLED7") (pin "2") (pinfunction "2_2") (pintype "passive"))
      (node (ref "RSENSE") (pin "1") (pinfunction "1_1") (pintype "passive"))
      (node (ref "RSENSEN") (pin "1") (pinfunction "1_1") (pintype "passive"))
      (node (ref "R_BAT") (pin "2") (pinfunction "2_2") (pintype "passive"))
      (node (ref "R_LCD2") (pin "1") (pinfunction "1_1") (pintype "passive"))
      (node (ref "R_PD_SEL") (pin "1") (pinfunction "1_1") (pintype "passive"))
      (node (ref "R_USB") (pin "2") (pinfunction "2_2") (pintype "passive"))
      (node (ref "R_VCC") (pin "2") (pinfunction "2_2") (pintype "passive"))
      (node (ref "SPI") (pin "6") (pinfunction "6_6") (pintype "bidirectional"))
    )
    (net (code "93") (name "Net-(ATMEGA2560-(A8)PC0)") (class "Default")
      (node (ref "ATMEGA2560") (pin "53") (pinfunction "(A8)PC0_53") (pintype "bidirectional"))
      (node (ref "LED0") (pin "A") (pinfunction "A_A") (pintype "passive"))
    )
    (net (code "94") (name "Net-(ATMEGA2560-(A9)PC1)") (class "Default")
      (node (ref "ATMEGA2560") (pin "54") (pinfunction "(A9)PC1_54") (pintype "bidirectional"))
      (node (ref "LED1") (pin "A") (pinfunction "A_A") (pintype "passive"))
    )
    (net (code "95") (name "Net-(ATMEGA2560-(A10)PC2)") (class "Default")
      (node (ref "ATMEGA2560") (pin "55") (pinfunction "(A10)PC2_55") (pintype "bidirectional"))
      (node (ref "LED2") (pin "A") (pinfunction "A_A") (pintype "passive"))
    )
    (net (code "96") (name "Net-(ATMEGA2560-(A11)PC3)") (class "Default")
      (node (ref "ATMEGA2560") (pin "56") (pinfunction "(A11)PC3_56") (pintype "bidirectional"))
      (node (ref "LED3") (pin "A") (pinfunction "A_A") (pintype "passive"))
    )
    (net (code "97") (name "Net-(ATMEGA2560-(A12)PC4)") (class "Default")
      (node (ref "ATMEGA2560") (pin "57") (pinfunction "(A12)PC4_57") (pintype "bidirectional"))
      (node (ref "LED4") (pin "A") (pinfunction "A_A") (pintype "passive"))
    )
    (net (code "98") (name "Net-(ATMEGA2560-(A13)PC5)") (class "Default")
      (node (ref "ATMEGA2560") (pin "58") (pinfunction "(A13)PC5_58") (pintype "bidirectional"))
      (node (ref "LED5") (pin "A") (pinfunction "A_A") (pintype "passive"))
    )
    (net (code "99") (name "Net-(ATMEGA2560-(A14)PC6)") (class "Default")
      (node (ref "ATMEGA2560") (pin "59") (pinfunction "(A14)PC6_59") (pintype "bidirectional"))
      (node (ref "LED6") (pin "A") (pinfunction "A_A") (pintype "passive"))
    )
    (net (code "100") (name "Net-(ATMEGA2560-(A15)PC7)") (class "Default")
      (node (ref "ATMEGA2560") (pin "60") (pinfunction "(A15)PC7_60") (pintype "bidirectional"))
      (node (ref "LED7") (pin "A") (pinfunction "A_A") (pintype "passive"))
    )
    (net (code "101") (name "Net-(ATMEGA2560-AREF)") (class "Default")
      (node (ref "ATMEGA2560") (pin "98") (pinfunction "AREF_98") (pintype "bidirectional"))
      (node (ref "C_AREF") (pin "1") (pinfunction "1_1") (pintype "passive"))
    )
    (net (code "102") (name "Net-(ATMEGA2560-AVCC)") (class "Default")
      (node (ref "ATMEGA2560") (pin "100") (pinfunction "AVCC_100") (pintype "power_in"))
      (node (ref "C_AVCC") (pin "1") (pinfunction "1_1") (pintype "passive"))
      (node (ref "L1") (pin "2") (pinfunction "2_2") (pintype "passive"))
    )
    (net (code "103") (name "Net-(ATMEGA2560-XTAL1)") (class "Default")
      (node (ref "16MHZ") (pin "1") (pinfunction "1_1") (pintype "passive"))
      (node (ref "ATMEGA2560") (pin "34") (pinfunction "XTAL1_34") (pintype "input"))
      (node (ref "C_CRY1") (pin "2") (pinfunction "2_2") (pintype "passive"))
    )
    (net (code "104") (name "Net-(ATMEGA2560-XTAL2)") (class "Default")
      (node (ref "16MHZ") (pin "2") (pinfunction "2_2") (pintype "passive"))
      (node (ref "ATMEGA2560") (pin "33") (pinfunction "XTAL2_33") (pintype "output"))
      (node (ref "C_CRY2") (pin "2") (pinfunction "2_2") (pintype "passive"))
    )
    (net (code "105") (name "Net-(BAT-MONIT-PadP$2)") (class "Default")
      (node (ref "BAT-MONIT") (pin "P$2") (pinfunction "P$2_P$2") (pintype "bidirectional"))
      (node (ref "RIN1") (pin "1") (pinfunction "1_1") (pintype "passive"))
    )
    (net (code "106") (name "Net-(BAT-MONIT-PadP$3)") (class "Default")
      (node (ref "BAT-MONIT") (pin "P$3") (pinfunction "P$3_P$3") (pintype "bidirectional"))
      (node (ref "RIN2") (pin "1") (pinfunction "1_1") (pintype "passive"))
    )
    (net (code "107") (name "Net-(BAT-MONIT-PadP$4)") (class "Default")
      (node (ref "BAT-MONIT") (pin "P$4") (pinfunction "P$4_P$4") (pintype "bidirectional"))
      (node (ref "JP4") (pin "1") (pinfunction "1_1") (pintype "passive"))
      (node (ref "RIN3") (pin "1") (pinfunction "1_1") (pintype "passive"))
    )
    (net (code "108") (name "Net-(BAT-MONIT-PadP$5)") (class "Default")
      (node (ref "BAT-MONIT") (pin "P$5") (pinfunction "P$5_P$5") (pintype "bidirectional"))
      (node (ref "JP4") (pin "2") (pinfunction "2_2") (pintype "passive"))
      (node (ref "JP5") (pin "1") (pinfunction "1_1") (pintype "passive"))
      (node (ref "RIN4") (pin "1") (pinfunction "1_1") (pintype "passive"))
    )
    (net (code "109") (name "Net-(BAT-MONIT-PadP$6)") (class "Default")
      (node (ref "BAT-MONIT") (pin "P$6") (pinfunction "P$6_P$6") (pintype "bidirectional"))
      (node (ref "JP5") (pin "2") (pinfunction "2_2") (pintype "passive"))
      (node (ref "JP6") (pin "1") (pinfunction "1_1") (pintype "passive"))
      (node (ref "RIN5") (pin "1") (pinfunction "1_1") (pintype "passive"))
    )
    (net (code "110") (name "Net-(BAT-PadC)") (class "Default")
      (node (ref "BAT") (pin "C") (pinfunction "C_C") (pintype "passive"))
      (node (ref "R_BAT") (pin "1") (pinfunction "1_1") (pintype "passive"))
    )
    (net (code "111") (name "Net-(BQ76925-BAT)") (class "Default")
      (node (ref "BQ76925") (pin "1") (pinfunction "VCTL_1") (pintype "output"))
      (node (ref "BQ76925") (pin "2") (pinfunction "BAT_2") (pintype "power_in"))
      (node (ref "CBAT") (pin "1") (pinfunction "1_1") (pintype "passive"))
      (node (ref "RBAT") (pin "2") (pinfunction "2_2") (pintype "passive"))
    )
    (net (code "112") (name "Net-(BQ76925-SENSEN)") (class "Default")
      (node (ref "BQ76925") (pin "11") (pinfunction "SENSEN_11") (pintype "input"))
      (node (ref "CSENSE") (pin "1") (pinfunction "1_1") (pintype "passive"))
      (node (ref "RSENSEN") (pin "2") (pinfunction "2_2") (pintype "passive"))
    )
    (net (code "113") (name "Net-(BQ76925-SENSEP)") (class "Default")
      (node (ref "BQ76925") (pin "12") (pinfunction "SENSEP_12") (pintype "input"))
      (node (ref "CSENSE") (pin "2") (pinfunction "2_2") (pintype "passive"))
      (node (ref "RSENSEP") (pin "2") (pinfunction "2_2") (pintype "passive"))
    )
    (net (code "114") (name "Net-(BQ76925-VC0)") (class "Default")
      (node (ref "BQ76925") (pin "9") (pinfunction "VC0_9") (pintype "input"))
      (node (ref "CIN") (pin "1") (pinfunction "1_1") (pintype "passive"))
      (node (ref "RIN") (pin "2") (pinfunction "2_2") (pintype "passive"))
    )
    (net (code "115") (name "Net-(BQ76925-VC1)") (class "Default")
      (node (ref "BQ76925") (pin "8") (pinfunction "VC1_8") (pintype "input"))
      (node (ref "CIN1") (pin "1") (pinfunction "1_1") (pintype "passive"))
      (node (ref "RIN1") (pin "2") (pinfunction "2_2") (pintype "passive"))
    )
    (net (code "116") (name "Net-(BQ76925-VC2)") (class "Default")
      (node (ref "BQ76925") (pin "7") (pinfunction "VC2_7") (pintype "input"))
      (node (ref "CIN2") (pin "1") (pinfunction "1_1") (pintype "passive"))
      (node (ref "RIN2") (pin "2") (pinfunction "2_2") (pintype "passive"))
    )
    (net (code "117") (name "Net-(BQ76925-VC3)") (class "Default")
      (node (ref "BQ76925") (pin "6") (pinfunction "VC3_6") (pintype "input"))
      (node (ref "CIN3") (pin "1") (pinfunction "1_1") (pintype "passive"))
      (node (ref "RIN3") (pin "2") (pinfunction "2_2") (pintype "passive"))
    )
    (net (code "118") (name "Net-(BQ76925-VC4)") (class "Default")
      (node (ref "BQ76925") (pin "5") (pinfunction "VC4_5") (pintype "input"))
      (node (ref "CIN4") (pin "1") (pinfunction "1_1") (pintype "passive"))
      (node (ref "RIN4") (pin "2") (pinfunction "2_2") (pintype "passive"))
    )
    (net (code "119") (name "Net-(BQ76925-VC5)") (class "Default")
      (node (ref "BQ76925") (pin "4") (pinfunction "VC5_4") (pintype "input"))
      (node (ref "CIN5") (pin "1") (pinfunction "1_1") (pintype "passive"))
      (node (ref "RIN5") (pin "2") (pinfunction "2_2") (pintype "passive"))
    )
    (net (code "120") (name "Net-(BQ76925-VC6)") (class "Default")
      (node (ref "BQ76925") (pin "3") (pinfunction "VC6_3") (pintype "input"))
      (node (ref "CIN6") (pin "1") (pinfunction "1_1") (pintype "passive"))
      (node (ref "RIN6") (pin "2") (pinfunction "2_2") (pintype "passive"))
    )
    (net (code "121") (name "Net-(BUTT_RESET-1-Pad2)") (class "Default")
      (node (ref "BUTT_RESET") (pin "1") (pinfunction "1_1") (pintype "passive"))
      (node (ref "BUTT_RESET") (pin "2") (pinfunction "1_2") (pintype "passive"))
      (node (ref "R_RES") (pin "2") (pinfunction "2_2") (pintype "passive"))
    )
    (net (code "122") (name "Net-(D1-K)") (class "Default")
      (node (ref "D1") (pin "2") (pinfunction "K_2") (pintype "passive"))
      (node (ref "L2") (pin "P$1") (pinfunction "1_P$1") (pintype "passive"))
      (node (ref "M1") (pin "5") (pinfunction "DRAIN_2_5") (pintype "passive"))
      (node (ref "M1") (pin "6") (pinfunction "DRAIN_2_6") (pintype "passive"))
      (node (ref "M1") (pin "7") (pinfunction "DRAIN_2_7") (pintype "passive"))
      (node (ref "M1") (pin "8") (pinfunction "DRAIN_2_8") (pintype "passive"))
      (node (ref "M1") (pin "9") (pinfunction "DRAIN_2_9") (pintype "passive"))
    )
    (net (code "123") (name "Net-(INV-Y)") (class "Default")
      (node (ref "INV") (pin "4") (pinfunction "Y_4") (pintype "bidirectional"))
      (node (ref "Q_SEL2") (pin "1") (pinfunction "G_1") (pintype "passive"))
      (node (ref "R_PD_SEL") (pin "2") (pinfunction "2_2") (pintype "passive"))
    )
    (net (code "124") (name "Net-(LED0-PadC)") (class "Default")
      (node (ref "LED0") (pin "C") (pinfunction "C_C") (pintype "passive"))
      (node (ref "RLED0") (pin "1") (pinfunction "1_1") (pintype "passive"))
    )
    (net (code "125") (name "Net-(LED1-PadC)") (class "Default")
      (node (ref "LED1") (pin "C") (pinfunction "C_C") (pintype "passive"))
      (node (ref "RLED1") (pin "1") (pinfunction "1_1") (pintype "passive"))
    )
    (net (code "126") (name "Net-(LED2-PadC)") (class "Default")
      (node (ref "LED2") (pin "C") (pinfunction "C_C") (pintype "passive"))
      (node (ref "RLED2") (pin "1") (pinfunction "1_1") (pintype "passive"))
    )
    (net (code "127") (name "Net-(LED3-PadC)") (class "Default")
      (node (ref "LED3") (pin "C") (pinfunction "C_C") (pintype "passive"))
      (node (ref "RLED3") (pin "1") (pinfunction "1_1") (pintype "passive"))
    )
    (net (code "128") (name "Net-(LED4-PadC)") (class "Default")
      (node (ref "LED4") (pin "C") (pinfunction "C_C") (pintype "passive"))
      (node (ref "RLED4") (pin "1") (pinfunction "1_1") (pintype "passive"))
    )
    (net (code "129") (name "Net-(LED5-PadC)") (class "Default")
      (node (ref "LED5") (pin "C") (pinfunction "C_C") (pintype "passive"))
      (node (ref "RLED5") (pin "1") (pinfunction "1_1") (pintype "passive"))
    )
    (net (code "130") (name "Net-(LED6-PadC)") (class "Default")
      (node (ref "LED6") (pin "C") (pinfunction "C_C") (pintype "passive"))
      (node (ref "RLED6") (pin "1") (pinfunction "1_1") (pintype "passive"))
    )
    (net (code "131") (name "Net-(LED7-PadC)") (class "Default")
      (node (ref "LED7") (pin "C") (pinfunction "C_C") (pintype "passive"))
      (node (ref "RLED7") (pin "1") (pinfunction "1_1") (pintype "passive"))
    )
    (net (code "132") (name "Net-(LM5085-ADJ)") (class "Default")
      (node (ref "CADJ") (pin "2") (pinfunction "2_2") (pintype "passive"))
      (node (ref "LM5085") (pin "1") (pinfunction "ADJ_1") (pintype "passive"))
      (node (ref "RADJ") (pin "2") (pinfunction "2_2") (pintype "passive"))
    )
    (net (code "133") (name "Net-(LM5085-FB)") (class "Default")
      (node (ref "CFF") (pin "2") (pinfunction "2_2") (pintype "passive"))
      (node (ref "LM5085") (pin "3") (pinfunction "FB_3") (pintype "passive"))
      (node (ref "RFB1") (pin "1") (pinfunction "1_1") (pintype "passive"))
      (node (ref "RFB2") (pin "2") (pinfunction "2_2") (pintype "passive"))
    )
    (net (code "134") (name "Net-(LM5085-ISEN)") (class "Default")
      (node (ref "LM5085") (pin "5") (pinfunction "ISEN_5") (pintype "passive"))
      (node (ref "M1") (pin "1") (pinfunction "SOURCE_2_1") (pintype "passive"))
      (node (ref "M1") (pin "2") (pinfunction "SOURCE_2_2") (pintype "passive"))
      (node (ref "M1") (pin "3") (pinfunction "SOURCE_2_3") (pintype "passive"))
      (node (ref "RSNS") (pin "2") (pinfunction "2_2") (pintype "passive"))
    )
    (net (code "135") (name "Net-(LM5085-PGATE)") (class "Default")
      (node (ref "LM5085") (pin "6") (pinfunction "PGATE_6") (pintype "passive"))
      (node (ref "M1") (pin "4") (pinfunction "GATE_4") (pintype "passive"))
    )
    (net (code "136") (name "Net-(LM5085-RT)") (class "Default")
      (node (ref "LM5085") (pin "2") (pinfunction "RT_2") (pintype "passive"))
      (node (ref "RT") (pin "2") (pinfunction "2_2") (pintype "passive"))
    )
    (net (code "137") (name "Net-(LM5085-VCC)") (class "Default")
      (node (ref "CVCC") (pin "2") (pinfunction "2_2") (pintype "passive"))
      (node (ref "LM5085") (pin "7") (pinfunction "VCC_7") (pintype "passive"))
    )
    (net (code "138") (name "Net-(LM7805-IN)") (class "Default")
      (node (ref "CI_78") (pin "1") (pinfunction "1_1") (pintype "passive"))
      (node (ref "LM7805") (pin "1") (pinfunction "IN_1") (pintype "bidirectional"))
      (node (ref "Q_SEL1") (pin "2") (pinfunction "S_2") (pintype "passive"))
    )
    (net (code "139") (name "Net-(PROGRAMMER10-Pad1)") (class "Default")
      (node (ref "PROGRAMMER10") (pin "1") (pinfunction "1_1") (pintype "passive"))
      (node (ref "RSPI1") (pin "2") (pinfunction "2_2") (pintype "passive"))
    )
    (net (code "140") (name "Net-(PROGRAMMER10-Pad5)") (class "Default")
      (node (ref "PROGRAMMER10") (pin "5") (pinfunction "5_5") (pintype "passive"))
      (node (ref "RSPI2") (pin "2") (pinfunction "2_2") (pintype "passive"))
    )
    (net (code "141") (name "Net-(PROGRAMMER10-Pad7)") (class "Default")
      (node (ref "PROGRAMMER10") (pin "7") (pinfunction "7_7") (pintype "passive"))
      (node (ref "RSPI3") (pin "2") (pinfunction "2_2") (pintype "passive"))
    )
    (net (code "142") (name "Net-(PROGRAMMER10-Pad9)") (class "Default")
      (node (ref "PROGRAMMER10") (pin "9") (pinfunction "9_9") (pintype "passive"))
      (node (ref "RSPI4") (pin "2") (pinfunction "2_2") (pintype "passive"))
    )
    (net (code "143") (name "Net-(Q_SEL1-G)") (class "Default")
      (node (ref "Q_SEL1") (pin "1") (pinfunction "G_1") (pintype "passive"))
      (node (ref "Q_SEL2") (pin "3") (pinfunction "D_3") (pintype "passive"))
      (node (ref "R_PU_SEL") (pin "1") (pinfunction "1_1") (pintype "passive"))
    )
    (net (code "144") (name "Net-(RSPI5-Pad2)") (class "Default")
      (node (ref "RSPI5") (pin "2") (pinfunction "2_2") (pintype "passive"))
      (node (ref "SPI") (pin "1") (pinfunction "1_1") (pintype "bidirectional"))
    )
    (net (code "145") (name "Net-(RSPI6-Pad2)") (class "Default")
      (node (ref "RSPI6") (pin "2") (pinfunction "2_2") (pintype "passive"))
      (node (ref "SPI") (pin "3") (pinfunction "3_3") (pintype "bidirectional"))
    )
    (net (code "146") (name "Net-(RSPI7-Pad2)") (class "Default")
      (node (ref "RSPI7") (pin "2") (pinfunction "2_2") (pintype "passive"))
      (node (ref "SPI") (pin "5") (pinfunction "5_5") (pintype "bidirectional"))
    )
    (net (code "147") (name "Net-(RSPI8-Pad2)") (class "Default")
      (node (ref "RSPI8") (pin "2") (pinfunction "2_2") (pintype "passive"))
      (node (ref "SPI") (pin "4") (pinfunction "4_4") (pintype "bidirectional"))
    )
    (net (code "148") (name "Net-(R_USB-Pad1)") (class "Default")
      (node (ref "R_USB") (pin "1") (pinfunction "1_1") (pintype "passive"))
      (node (ref "USB") (pin "C") (pinfunction "C_C") (pintype "passive"))
    )
    (net (code "149") (name "Net-(R_VCC-Pad1)") (class "Default")
      (node (ref "R_VCC") (pin "1") (pinfunction "1_1") (pintype "passive"))
      (node (ref "VCC") (pin "C") (pinfunction "C_C") (pintype "passive"))
    )
    (net (code "150") (name "VCC") (class "Default")
      (node (ref "ATMEGA2560") (pin "10") (pinfunction "VCC_10") (pintype "power_in"))
      (node (ref "ATMEGA2560") (pin "31") (pinfunction "VCC1_31") (pintype "power_in"))
      (node (ref "ATMEGA2560") (pin "61") (pinfunction "VCC2_61") (pintype "power_in"))
      (node (ref "ATMEGA2560") (pin "80") (pinfunction "VCC3_80") (pintype "power_in"))
      (node (ref "CO_78") (pin "1") (pinfunction "1_1") (pintype "passive"))
      (node (ref "C_DECO1") (pin "1") (pinfunction "1_1") (pintype "passive"))
      (node (ref "C_DECO2") (pin "1") (pinfunction "1_1") (pintype "passive"))
      (node (ref "C_DECO3") (pin "1") (pinfunction "1_1") (pintype "passive"))
      (node (ref "C_DECO4") (pin "1") (pinfunction "1_1") (pintype "passive"))
      (node (ref "D_PU_RES") (pin "C") (pinfunction "C_C") (pintype "passive"))
      (node (ref "D_SEL") (pin "C") (pinfunction "C_C") (pintype "passive"))
      (node (ref "I2C") (pin "1") (pinfunction "1_1") (pintype "passive"))
      (node (ref "IMU_BOARD") (pin "6") (pinfunction "6_6") (pintype "passive"))
      (node (ref "INV") (pin "5") (pinfunction "VCC_5") (pintype "bidirectional"))
      (node (ref "L1") (pin "1") (pinfunction "1_1") (pintype "passive"))
      (node (ref "LM7805") (pin "3") (pinfunction "OUT_3") (pintype "bidirectional"))
      (node (ref "PORTB") (pin "10") (pinfunction "10_10") (pintype "passive"))
      (node (ref "PORTD") (pin "10") (pinfunction "10_10") (pintype "passive"))
      (node (ref "PORTE") (pin "10") (pinfunction "10_10") (pintype "passive"))
      (node (ref "PORTF") (pin "10") (pinfunction "10_10") (pintype "passive"))
      (node (ref "PORTG") (pin "10") (pinfunction "10_10") (pintype "passive"))
      (node (ref "PORTG") (pin "8") (pinfunction "8_8") (pintype "passive"))
      (node (ref "PORTH") (pin "10") (pinfunction "10_10") (pintype "passive"))
      (node (ref "PORTJ") (pin "10") (pinfunction "10_10") (pintype "passive"))
      (node (ref "PORTK") (pin "10") (pinfunction "10_10") (pintype "passive"))
      (node (ref "PORTL") (pin "10") (pinfunction "10_10") (pintype "passive"))
      (node (ref "RADIO_CONTROLLER") (pin "10") (pinfunction "5V_10") (pintype "power_in"))
      (node (ref "RADIO_CONTROLLER") (pin "11") (pinfunction "5V_11") (pintype "power_in"))
      (node (ref "RADIO_CONTROLLER") (pin "12") (pinfunction "5V_12") (pintype "power_in"))
      (node (ref "RADIO_CONTROLLER") (pin "13") (pinfunction "5V_13") (pintype "power_in"))
      (node (ref "RADIO_CONTROLLER") (pin "14") (pinfunction "5V_14") (pintype "power_in"))
      (node (ref "RADIO_CONTROLLER") (pin "8") (pinfunction "5V_8") (pintype "power_in"))
      (node (ref "RADIO_CONTROLLER") (pin "9") (pinfunction "5V_9") (pintype "power_in"))
      (node (ref "RSCL") (pin "1") (pinfunction "1_1") (pintype "passive"))
      (node (ref "RSDA") (pin "1") (pinfunction "1_1") (pintype "passive"))
      (node (ref "R_LCD1") (pin "2") (pinfunction "2_2") (pintype "passive"))
      (node (ref "R_PU_RES") (pin "2") (pinfunction "2_2") (pintype "passive"))
      (node (ref "R_PU_SS") (pin "2") (pinfunction "2_2") (pintype "passive"))
      (node (ref "VCC") (pin "A") (pinfunction "A_A") (pintype "passive"))
    )
    (net (code "151") (name "V_BATT") (class "Default")
      (node (ref "BAT-MONIT") (pin "P$7") (pinfunction "P$7_P$7") (pintype "bidirectional"))
      (node (ref "CADJ") (pin "1") (pinfunction "1_1") (pintype "passive"))
      (node (ref "CIN_1") (pin "1") (pinfunction "1_1") (pintype "passive"))
      (node (ref "CIN_2") (pin "1") (pinfunction "1_1") (pintype "passive"))
      (node (ref "CVCC") (pin "1") (pinfunction "1_1") (pintype "passive"))
      (node (ref "JP6") (pin "2") (pinfunction "2_2") (pintype "passive"))
      (node (ref "LM5085") (pin "8") (pinfunction "VIN_8") (pintype "passive"))
      (node (ref "PUSH_BUTT") (pin "P$LOAD") (pinfunction "2_LOAD_P$LOAD") (pintype "bidirectional"))
      (node (ref "Q_SEL1") (pin "3") (pinfunction "D_3") (pintype "passive"))
      (node (ref "RADJ") (pin "1") (pinfunction "1_1") (pintype "passive"))
      (node (ref "RBAT") (pin "1") (pinfunction "1_1") (pintype "passive"))
      (node (ref "RIN6") (pin "1") (pinfunction "1_1") (pintype "passive"))
      (node (ref "RSNS") (pin "1") (pinfunction "1_1") (pintype "passive"))
      (node (ref "RT") (pin "1") (pinfunction "1_1") (pintype "passive"))
      (node (ref "R_PU_SEL") (pin "2") (pinfunction "2_2") (pintype "passive"))
    )
    (net (code "152") (name "V_USB") (class "Default")
      (node (ref "D_SEL") (pin "A") (pinfunction "A_A") (pintype "passive"))
      (node (ref "INV") (pin "2") (pinfunction "A_2") (pintype "bidirectional"))
      (node (ref "PROGRAMMER10") (pin "2") (pinfunction "2_2") (pintype "passive"))
      (node (ref "SPI") (pin "2") (pinfunction "2_2") (pintype "bidirectional"))
      (node (ref "USB") (pin "A") (pinfunction "A_A") (pintype "passive"))
    )
    (net (code "153") (name "unconnected-(BQ76925-VTB-Pad16)") (class "Default")
      (node (ref "BQ76925") (pin "16") (pinfunction "VTB_16") (pintype "output"))
    )
    (net (code "154") (name "unconnected-(INV-NC-Pad1)") (class "Default")
      (node (ref "INV") (pin "1") (pinfunction "NC_1") (pintype "bidirectional"))
    )
    (net (code "155") (name "unconnected-(PROGRAMMER10-Pad3)") (class "Default")
      (node (ref "PROGRAMMER10") (pin "3") (pinfunction "3_3") (pintype "passive"))
    )
    (net (code "156") (name "unconnected-(RADIO_CONTROLLER-7-Pad21)") (class "Default")
      (node (ref "RADIO_CONTROLLER") (pin "21") (pinfunction "7_21") (pintype "bidirectional"))
    )
  )
)
